# PCB-164D316B_sch.net
KiCad netlist of a schematic drawn in EAGLE
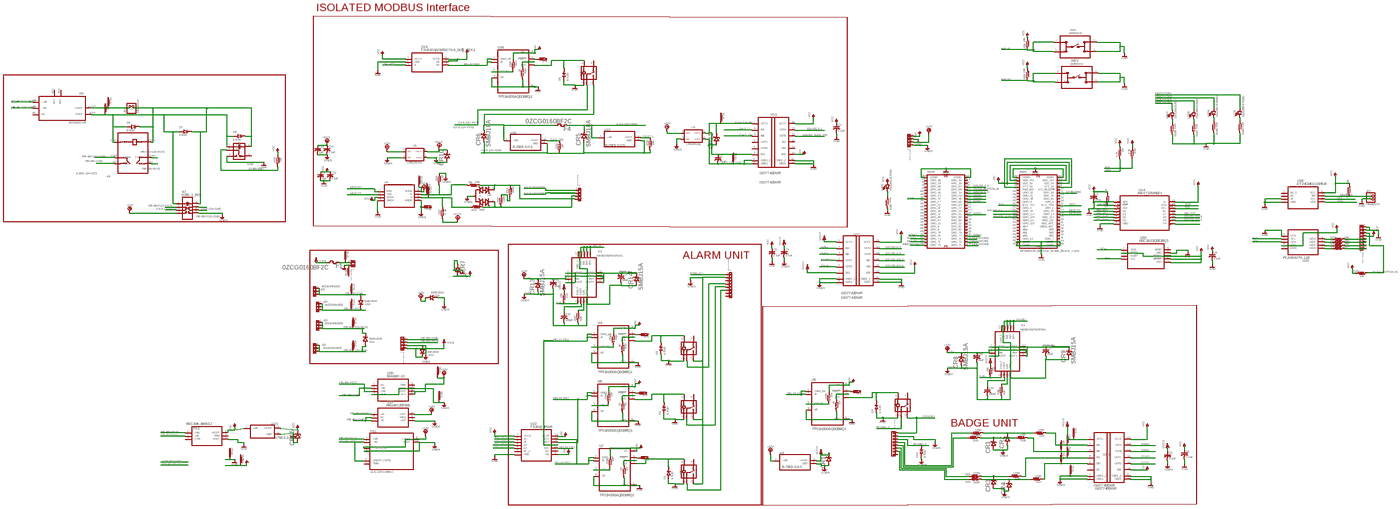
[diagram p0: schematic, sheet 1, overview]
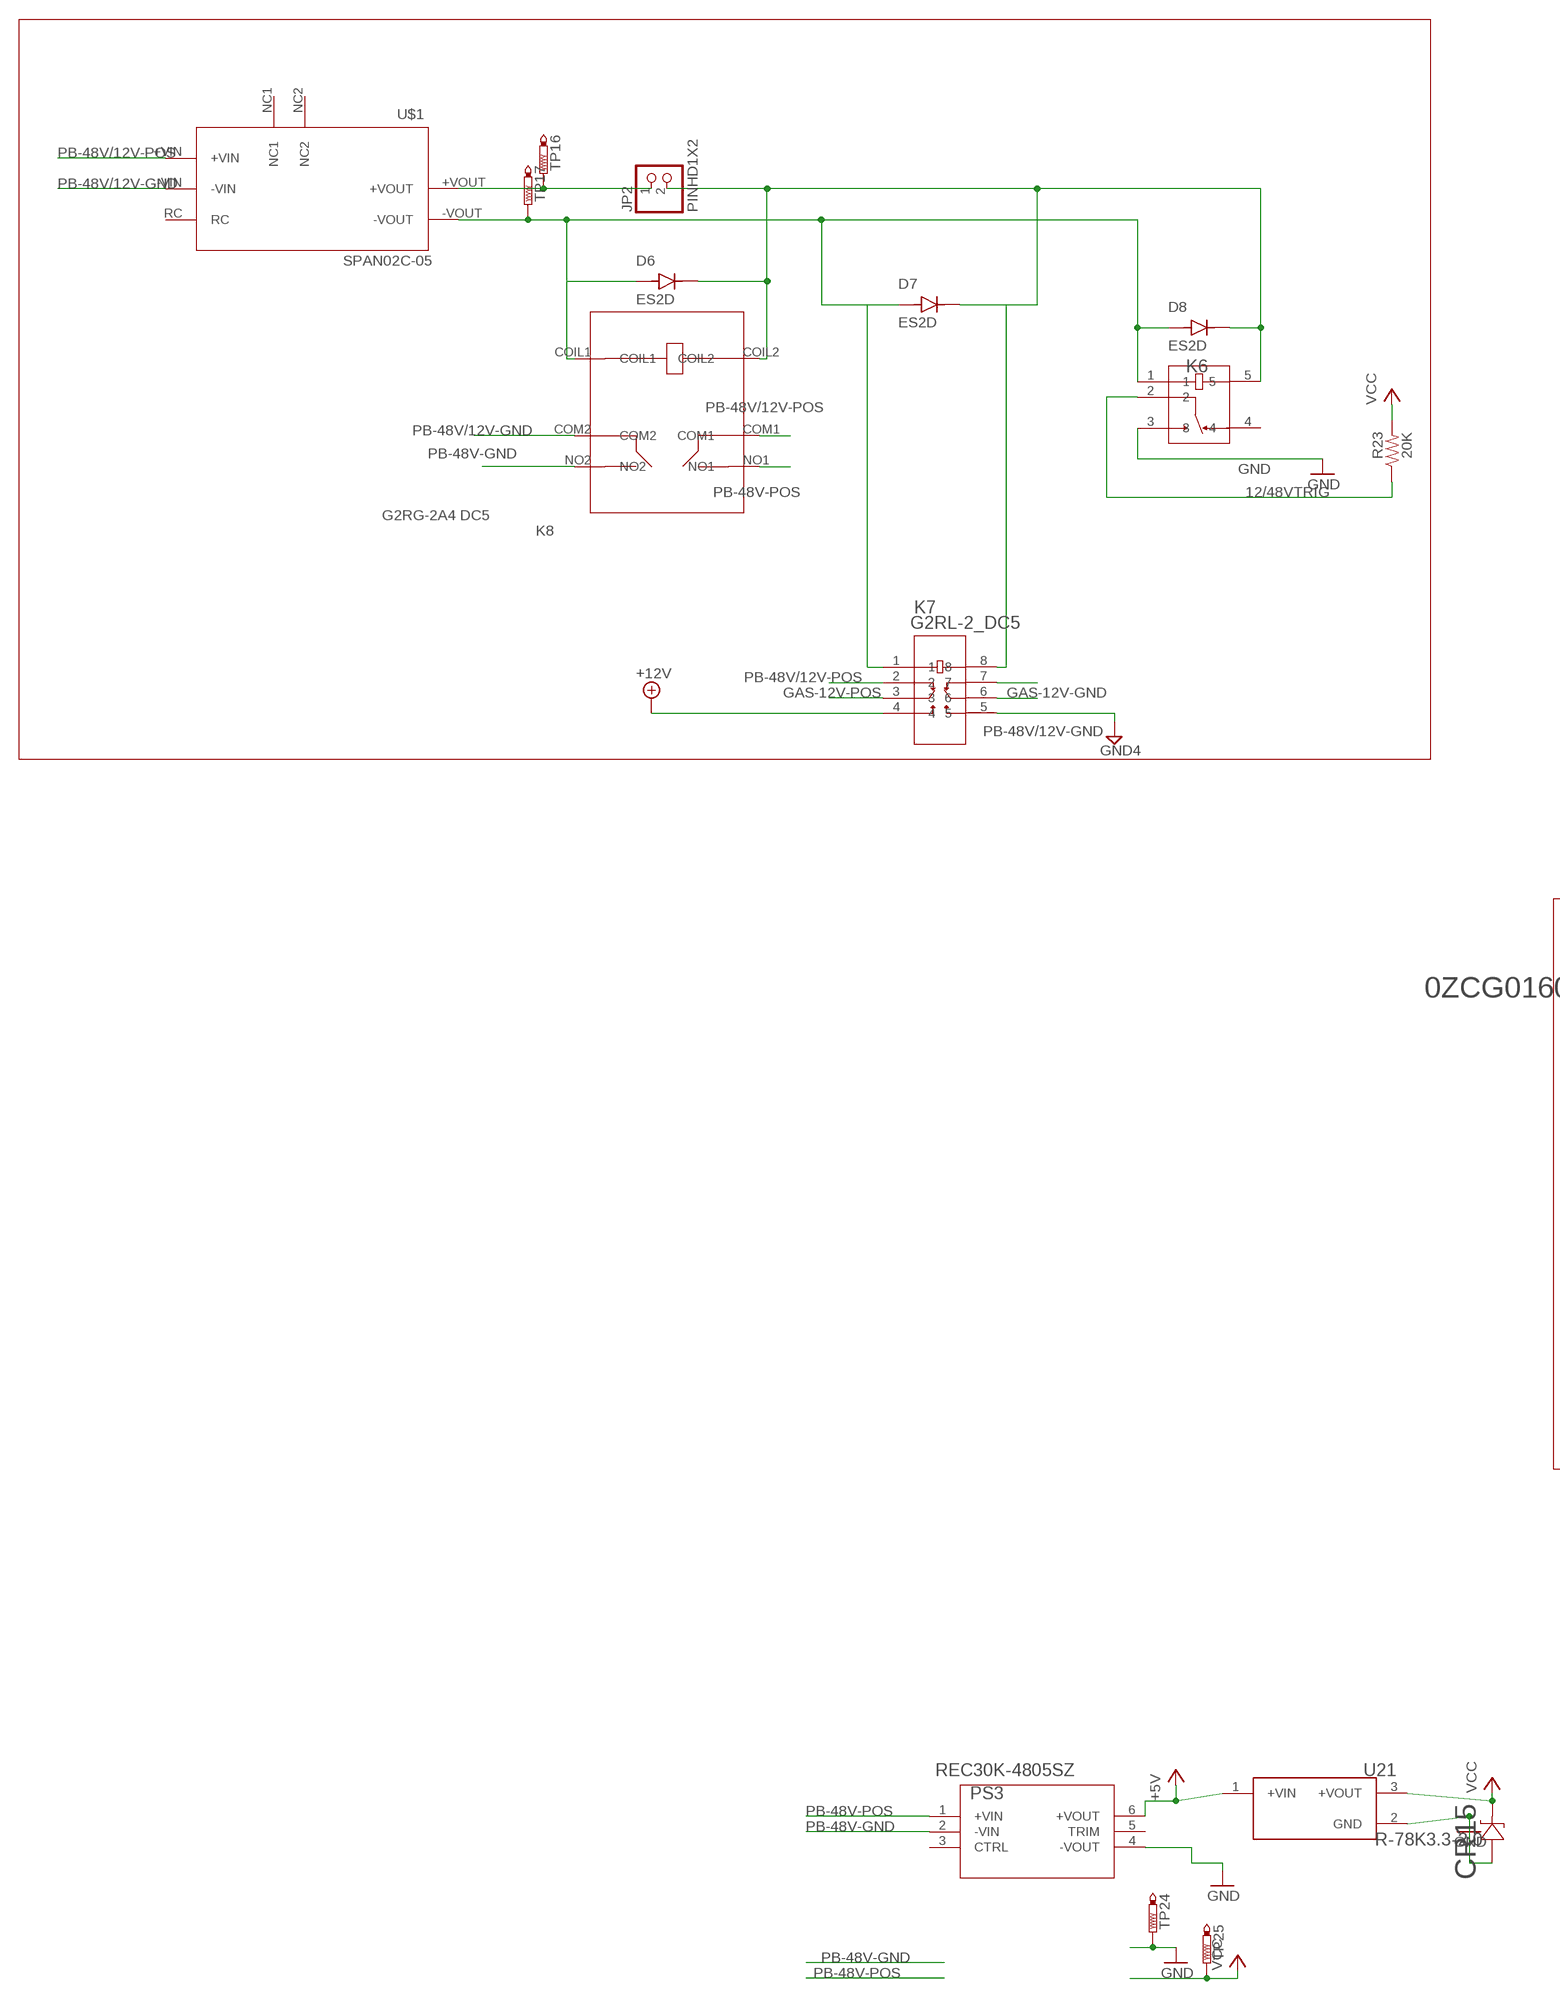
[diagram p1: schematic, sheet 1, part 1 of 4]
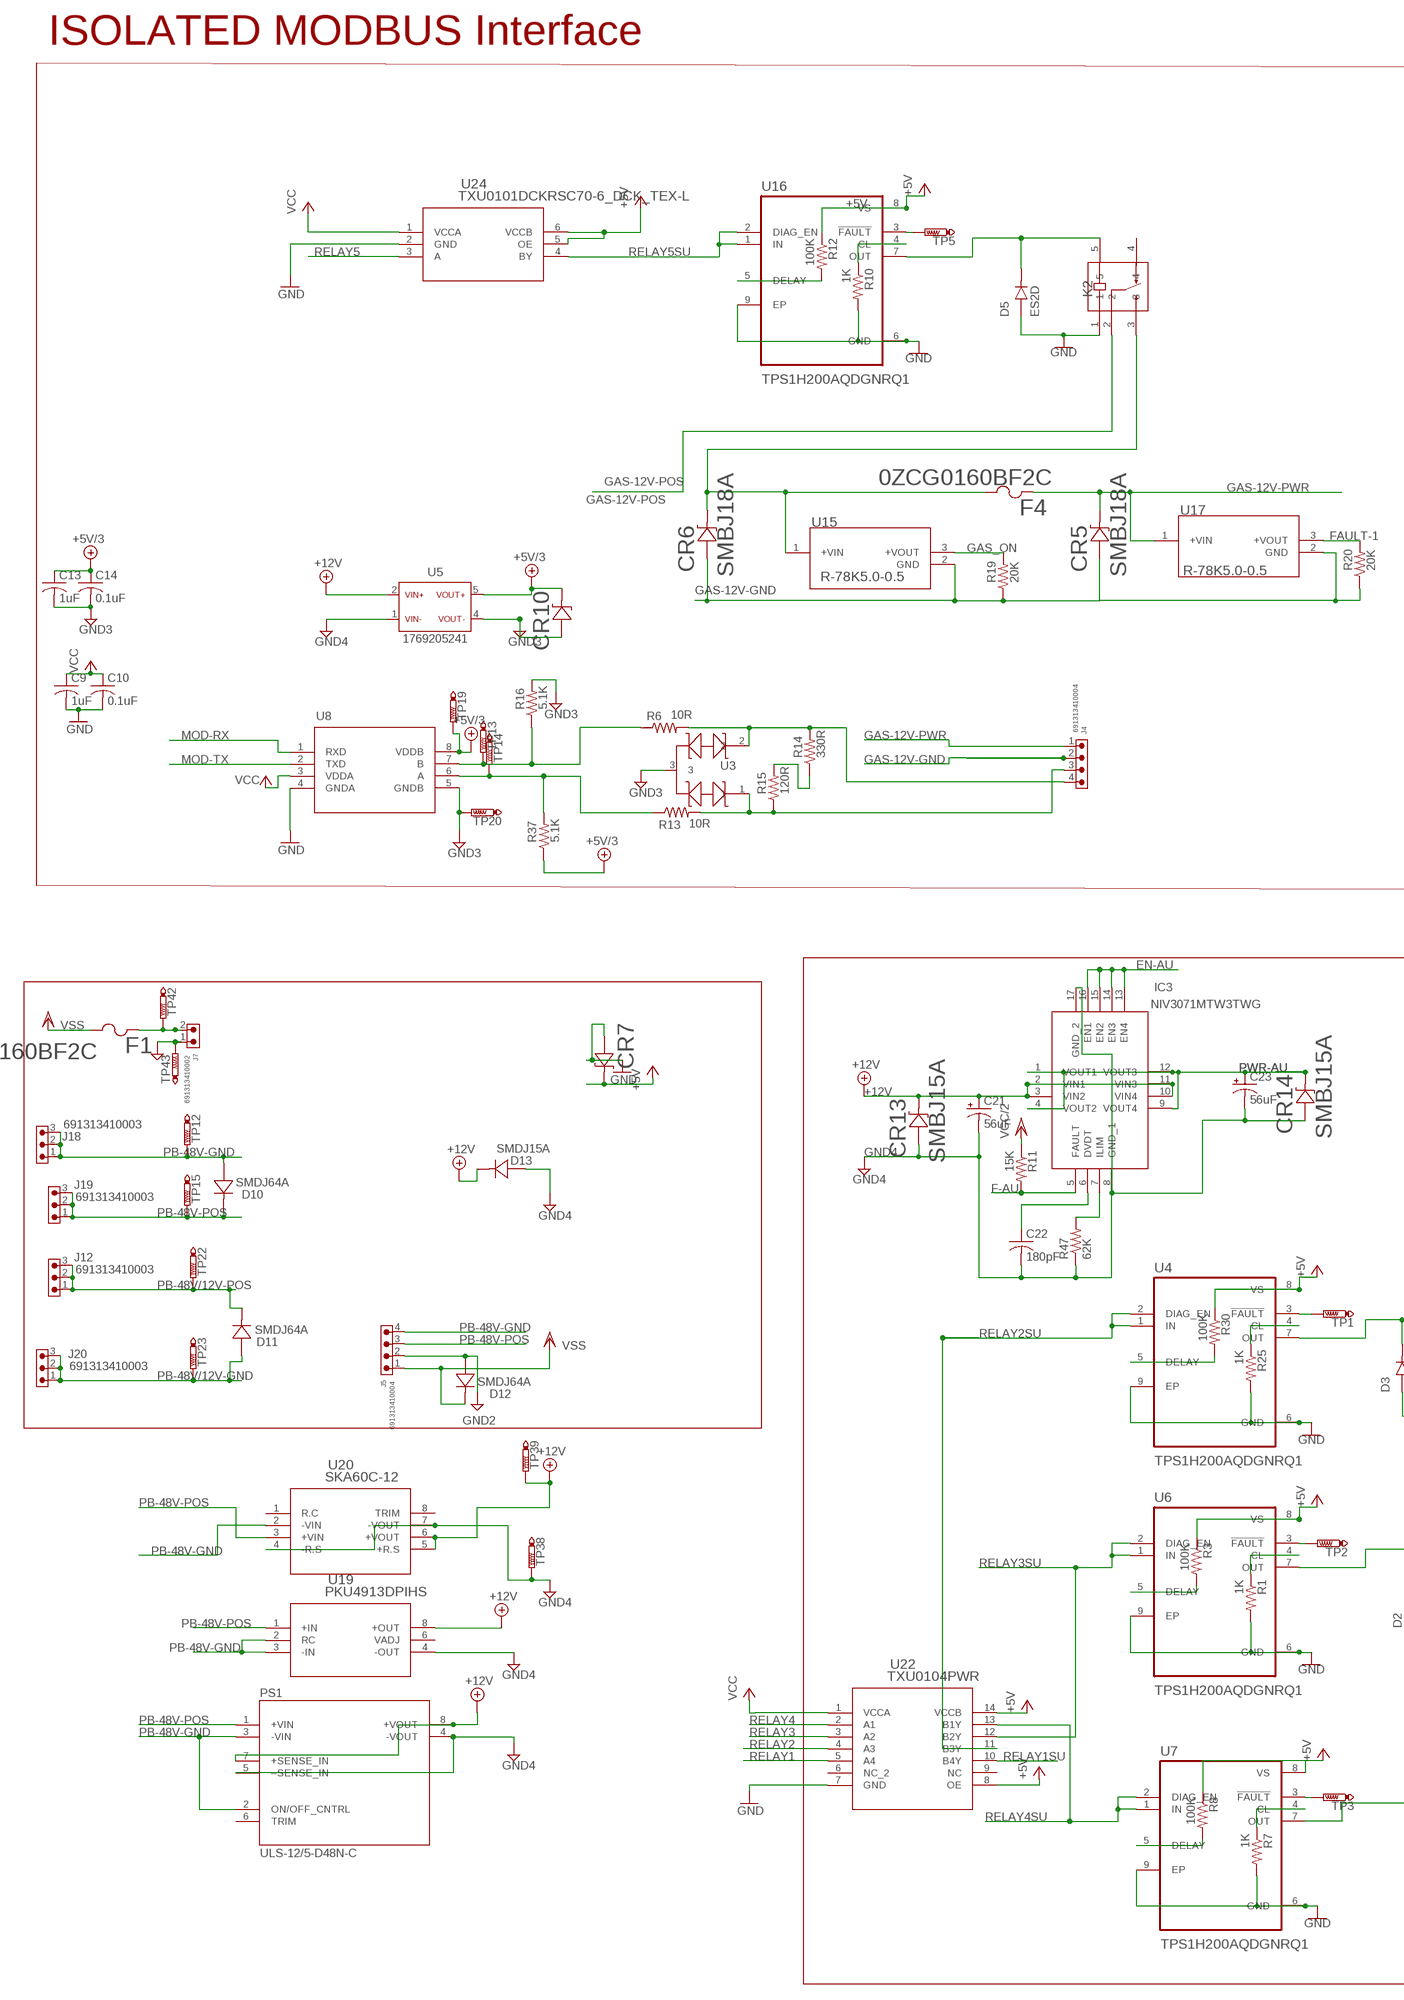
[diagram p2: schematic, sheet 1, part 2 of 4]
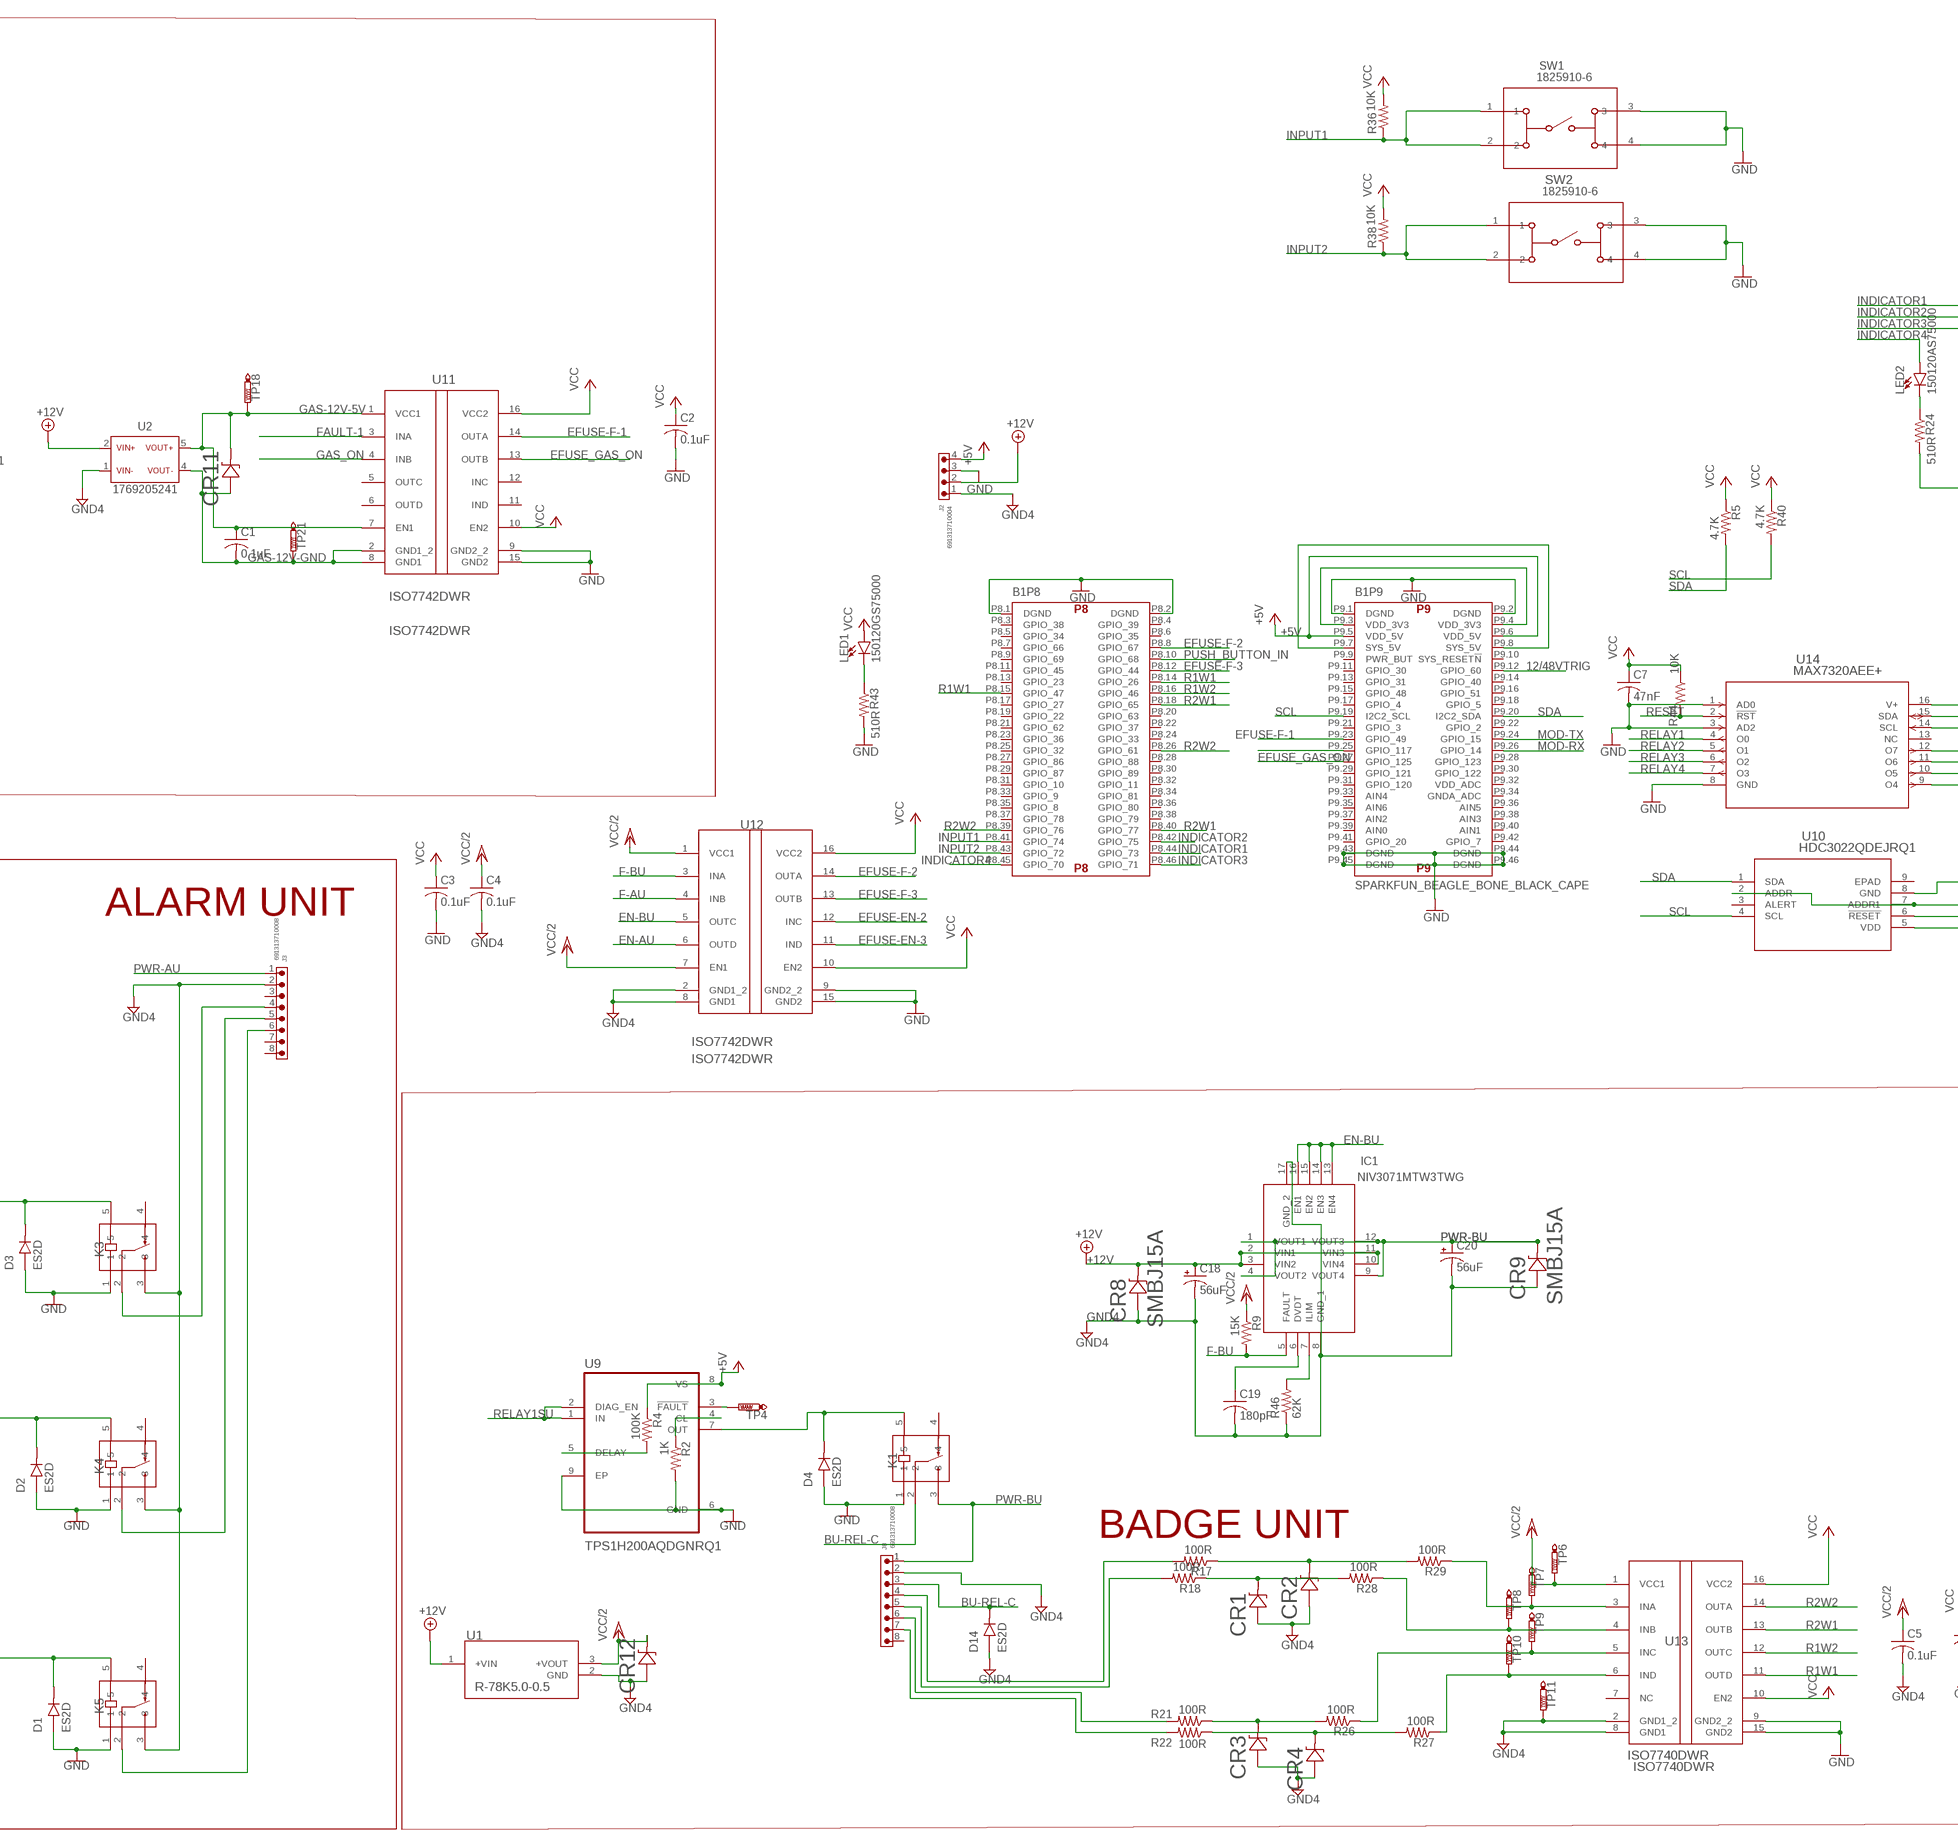
[diagram p3: schematic, sheet 1, part 3 of 4]
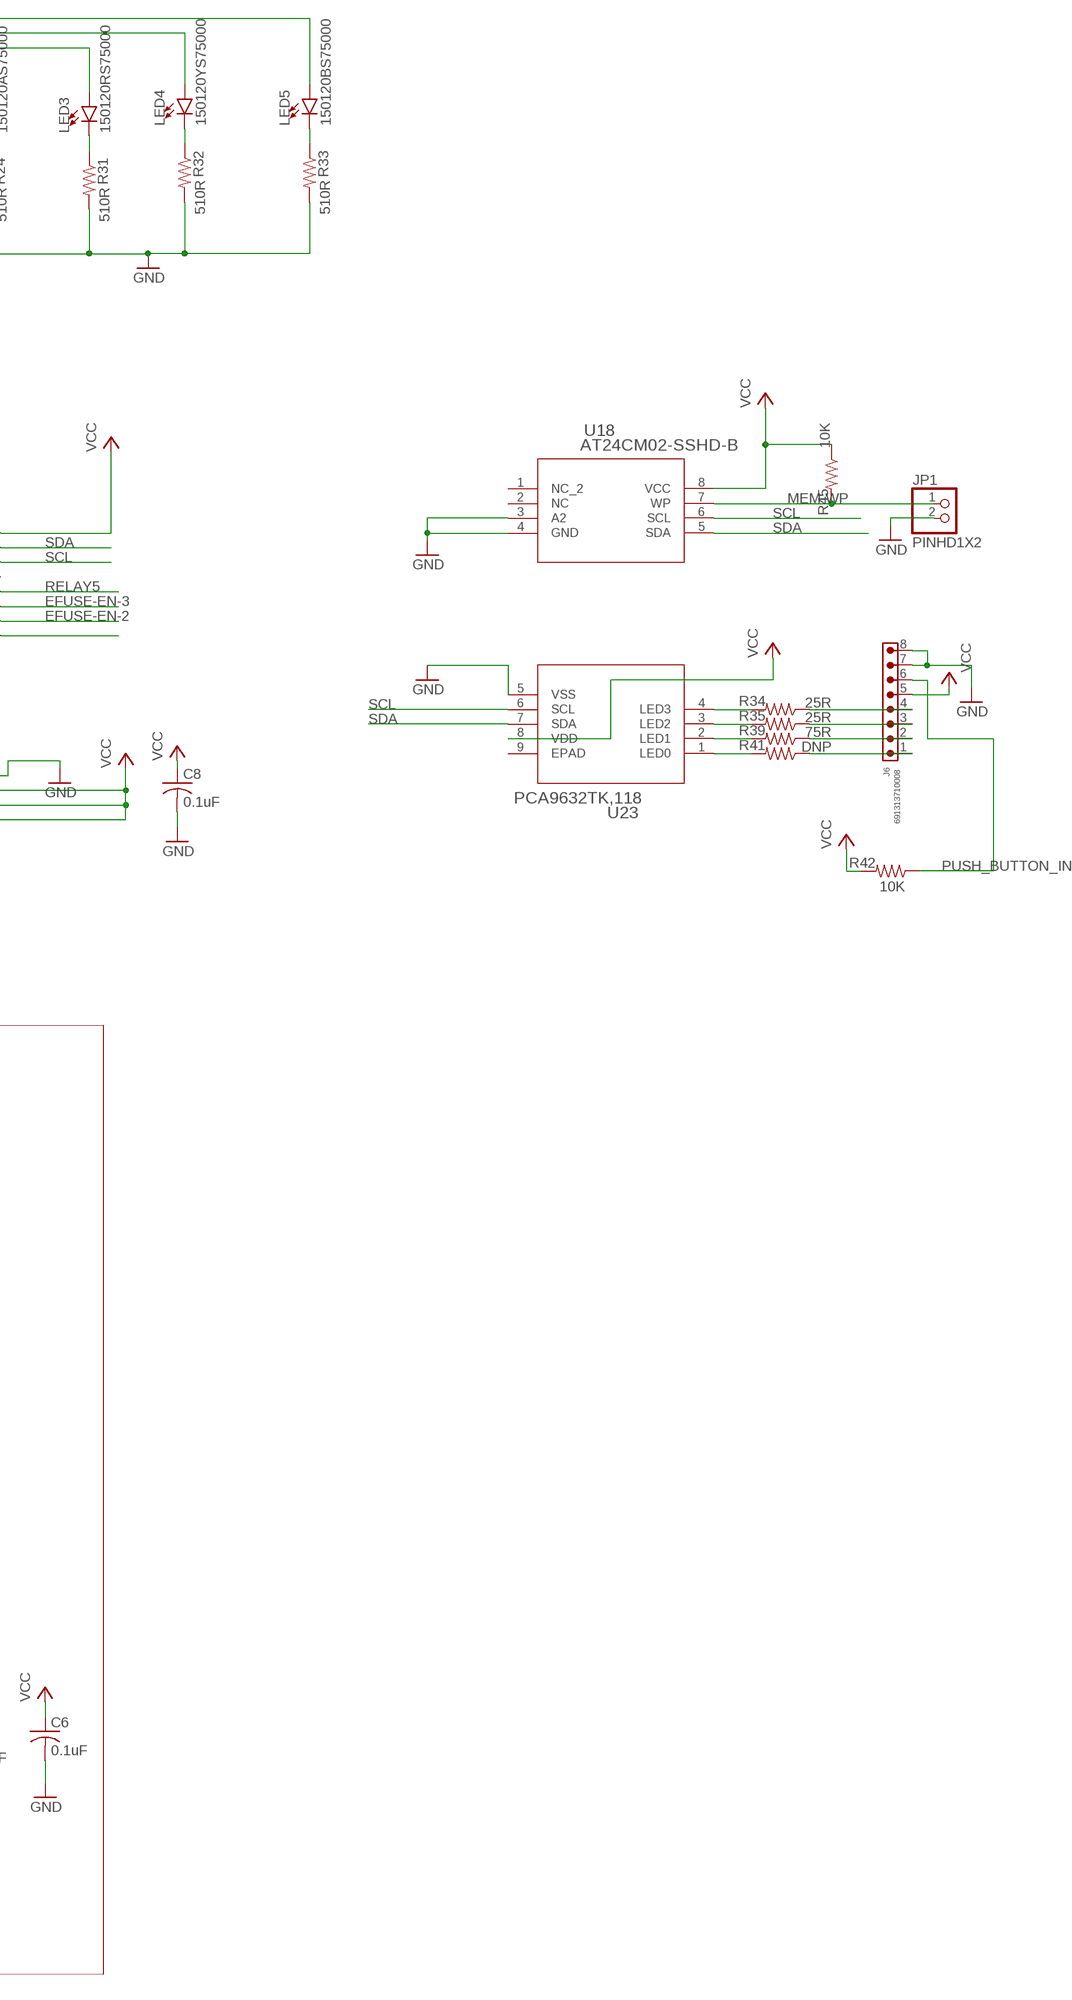
[diagram p4: schematic, sheet 1, part 4 of 4]

(export (version "E")
  (design (tool "Eeschema 10.0.6"))
  (components
    (comp (ref "B1")
      (value "SPARKFUN_BEAGLE_BONE_BLACK_CAPE")
      (footprint "eagle-import:BEAGLE_BONE_BLACK_CAPE")
      (libsource (lib "eagle-import") (part "SPARKFUN_BEAGLE_BONE_BLACK_CAPE"))
    )
    (comp (ref "C1")
      (value "0.1uF")
      (footprint "eagle-import:C1206")
      (libsource (lib "eagle-import") (part "C-USC1206"))
    )
    (comp (ref "C2")
      (value "0.1uF")
      (footprint "eagle-import:C1206")
      (libsource (lib "eagle-import") (part "C-USC1206"))
    )
    (comp (ref "C3")
      (value "0.1uF")
      (footprint "eagle-import:C1206")
      (libsource (lib "eagle-import") (part "C-USC1206"))
    )
    (comp (ref "C4")
      (value "0.1uF")
      (footprint "eagle-import:C1206")
      (libsource (lib "eagle-import") (part "C-USC1206"))
    )
    (comp (ref "C5")
      (value "0.1uF")
      (footprint "eagle-import:C1206")
      (libsource (lib "eagle-import") (part "C-USC1206"))
    )
    (comp (ref "C6")
      (value "0.1uF")
      (footprint "eagle-import:C1206")
      (libsource (lib "eagle-import") (part "C-USC1206"))
    )
    (comp (ref "C7")
      (value "47nF")
      (footprint "eagle-import:C1206")
      (libsource (lib "eagle-import") (part "C-USC1206"))
    )
    (comp (ref "C8")
      (value "0.1uF")
      (footprint "eagle-import:C1206")
      (libsource (lib "eagle-import") (part "C-USC1206"))
    )
    (comp (ref "C9")
      (value "1uF")
      (footprint "eagle-import:C1206")
      (libsource (lib "eagle-import") (part "C-USC1206"))
    )
    (comp (ref "C10")
      (value "0.1uF")
      (footprint "eagle-import:C1206")
      (libsource (lib "eagle-import") (part "C-USC1206"))
    )
    (comp (ref "C13")
      (value "1uF")
      (footprint "eagle-import:C1206")
      (libsource (lib "eagle-import") (part "C-USC1206"))
    )
    (comp (ref "C14")
      (value "0.1uF")
      (footprint "eagle-import:C1206")
      (libsource (lib "eagle-import") (part "C-USC1206"))
    )
    (comp (ref "C18")
      (value "56uF")
      (footprint "eagle-import:PANASONIC_C")
      (libsource (lib "eagle-import") (part "CPOL-USC"))
    )
    (comp (ref "C19")
      (value "180pF")
      (footprint "eagle-import:C1206")
      (libsource (lib "eagle-import") (part "C-USC1206"))
    )
    (comp (ref "C20")
      (value "56uF")
      (footprint "eagle-import:PANASONIC_C")
      (libsource (lib "eagle-import") (part "CPOL-USC"))
    )
    (comp (ref "C21")
      (value "56uF")
      (footprint "eagle-import:PANASONIC_C")
      (libsource (lib "eagle-import") (part "CPOL-USC"))
    )
    (comp (ref "C22")
      (value "180pF")
      (footprint "eagle-import:C1206")
      (libsource (lib "eagle-import") (part "C-USC1206"))
    )
    (comp (ref "C23")
      (value "56uF")
      (footprint "eagle-import:PANASONIC_C")
      (libsource (lib "eagle-import") (part "CPOL-USC"))
    )
    (comp (ref "CR1")
      (value "SMBJ6.0A")
      (footprint "eagle-import:DO-214AA(SMB_J-BEND)_LTF-M")
      (fields
        (field (name "MANUFACTURER_PART_NUMBER") "SMBJ5.0A")
        (field (name "COPYRIGHT") "Copyright (C) 2024 Ultra Librarian. All rights reserved.")
      )
      (libsource (lib "eagle-import") (part "SMBJ5.0ADO-214AA(SMB_J-BEND)_LTF-M"))
    )
    (comp (ref "CR2")
      (value "SMBJ6.0A")
      (footprint "eagle-import:DO-214AA(SMB_J-BEND)_LTF-M")
      (fields
        (field (name "MANUFACTURER_PART_NUMBER") "SMBJ5.0A")
        (field (name "COPYRIGHT") "Copyright (C) 2024 Ultra Librarian. All rights reserved.")
      )
      (libsource (lib "eagle-import") (part "SMBJ5.0ADO-214AA(SMB_J-BEND)_LTF-M"))
    )
    (comp (ref "CR3")
      (value "SMBJ6.0A")
      (footprint "eagle-import:DO-214AA(SMB_J-BEND)_LTF-M")
      (fields
        (field (name "MANUFACTURER_PART_NUMBER") "SMBJ5.0A")
        (field (name "COPYRIGHT") "Copyright (C) 2024 Ultra Librarian. All rights reserved.")
      )
      (libsource (lib "eagle-import") (part "SMBJ5.0ADO-214AA(SMB_J-BEND)_LTF-M"))
    )
    (comp (ref "CR4")
      (value "SMBJ6.0A")
      (footprint "eagle-import:DO-214AA(SMB_J-BEND)_LTF-M")
      (fields
        (field (name "MANUFACTURER_PART_NUMBER") "SMBJ5.0A")
        (field (name "COPYRIGHT") "Copyright (C) 2024 Ultra Librarian. All rights reserved.")
      )
      (libsource (lib "eagle-import") (part "SMBJ5.0ADO-214AA(SMB_J-BEND)_LTF-M"))
    )
    (comp (ref "CR5")
      (value "SMBJ18A")
      (footprint "eagle-import:DO-214AA(SMB_J-BEND)_LTF-M")
      (fields
        (field (name "MANUFACTURER_PART_NUMBER") "SMBJ5.0A")
        (field (name "COPYRIGHT") "Copyright (C) 2024 Ultra Librarian. All rights reserved.")
      )
      (libsource (lib "eagle-import") (part "SMBJ5.0ADO-214AA(SMB_J-BEND)_LTF-M"))
    )
    (comp (ref "CR6")
      (value "SMBJ18A")
      (footprint "eagle-import:DO-214AA(SMB_J-BEND)_LTF-M")
      (fields
        (field (name "MANUFACTURER_PART_NUMBER") "SMBJ5.0A")
        (field (name "COPYRIGHT") "Copyright (C) 2024 Ultra Librarian. All rights reserved.")
      )
      (libsource (lib "eagle-import") (part "SMBJ5.0ADO-214AA(SMB_J-BEND)_LTF-M"))
    )
    (comp (ref "CR7")
      (value "SMBJ6.0A")
      (footprint "eagle-import:DO-214AA(SMB_J-BEND)_LTF-M")
      (fields
        (field (name "MANUFACTURER_PART_NUMBER") "SMBJ5.0A")
        (field (name "COPYRIGHT") "Copyright (C) 2024 Ultra Librarian. All rights reserved.")
      )
      (libsource (lib "eagle-import") (part "SMBJ5.0ADO-214AA(SMB_J-BEND)_LTF-M"))
    )
    (comp (ref "CR8")
      (value "SMBJ15A")
      (footprint "eagle-import:DO-214AA(SMB_J-BEND)_LTF-M")
      (fields
        (field (name "MANUFACTURER_PART_NUMBER") "SMBJ5.0A")
        (field (name "COPYRIGHT") "Copyright (C) 2024 Ultra Librarian. All rights reserved.")
      )
      (libsource (lib "eagle-import") (part "SMBJ5.0ADO-214AA(SMB_J-BEND)_LTF-M"))
    )
    (comp (ref "CR9")
      (value "SMBJ15A")
      (footprint "eagle-import:DO-214AA(SMB_J-BEND)_LTF-M")
      (fields
        (field (name "MANUFACTURER_PART_NUMBER") "SMBJ5.0A")
        (field (name "COPYRIGHT") "Copyright (C) 2024 Ultra Librarian. All rights reserved.")
      )
      (libsource (lib "eagle-import") (part "SMBJ5.0ADO-214AA(SMB_J-BEND)_LTF-M"))
    )
    (comp (ref "CR10")
      (value "SMBJ6.0A")
      (footprint "eagle-import:DO-214AA(SMB_J-BEND)_LTF-M")
      (fields
        (field (name "MANUFACTURER_PART_NUMBER") "SMBJ5.0A")
        (field (name "COPYRIGHT") "Copyright (C) 2024 Ultra Librarian. All rights reserved.")
      )
      (libsource (lib "eagle-import") (part "SMBJ5.0ADO-214AA(SMB_J-BEND)_LTF-M"))
    )
    (comp (ref "CR11")
      (value "SMBJ6.0A")
      (footprint "eagle-import:DO-214AA(SMB_J-BEND)_LTF-M")
      (fields
        (field (name "MANUFACTURER_PART_NUMBER") "SMBJ5.0A")
        (field (name "COPYRIGHT") "Copyright (C) 2024 Ultra Librarian. All rights reserved.")
      )
      (libsource (lib "eagle-import") (part "SMBJ5.0ADO-214AA(SMB_J-BEND)_LTF-M"))
    )
    (comp (ref "CR12")
      (value "SMBJ6.0A")
      (footprint "eagle-import:DO-214AA(SMB_J-BEND)_LTF-M")
      (fields
        (field (name "MANUFACTURER_PART_NUMBER") "SMBJ5.0A")
        (field (name "COPYRIGHT") "Copyright (C) 2024 Ultra Librarian. All rights reserved.")
      )
      (libsource (lib "eagle-import") (part "SMBJ5.0ADO-214AA(SMB_J-BEND)_LTF-M"))
    )
    (comp (ref "CR13")
      (value "SMBJ15A")
      (footprint "eagle-import:DO-214AA(SMB_J-BEND)_LTF-M")
      (fields
        (field (name "MANUFACTURER_PART_NUMBER") "SMBJ5.0A")
        (field (name "COPYRIGHT") "Copyright (C) 2024 Ultra Librarian. All rights reserved.")
      )
      (libsource (lib "eagle-import") (part "SMBJ5.0ADO-214AA(SMB_J-BEND)_LTF-M"))
    )
    (comp (ref "CR14")
      (value "SMBJ15A")
      (footprint "eagle-import:DO-214AA(SMB_J-BEND)_LTF-M")
      (fields
        (field (name "MANUFACTURER_PART_NUMBER") "SMBJ5.0A")
        (field (name "COPYRIGHT") "Copyright (C) 2024 Ultra Librarian. All rights reserved.")
      )
      (libsource (lib "eagle-import") (part "SMBJ5.0ADO-214AA(SMB_J-BEND)_LTF-M"))
    )
    (comp (ref "CR15")
      (value "SMBJ6.0A")
      (footprint "eagle-import:DO-214AA(SMB_J-BEND)_LTF-M")
      (fields
        (field (name "MANUFACTURER_PART_NUMBER") "SMBJ5.0A")
        (field (name "COPYRIGHT") "Copyright (C) 2024 Ultra Librarian. All rights reserved.")
      )
      (libsource (lib "eagle-import") (part "SMBJ5.0ADO-214AA(SMB_J-BEND)_LTF-M"))
    )
    (comp (ref "D1")
      (value "ES2D")
      (footprint "eagle-import:DIOM4336X265N")
      (fields
        (field (name "DIGIKEY_PART_NUMBER") "1801-ES2DTR-ND")
        (field (name "MF") "Taiwan Semiconductor")
      )
      (libsource (lib "eagle-import") (part "ES2D"))
    )
    (comp (ref "D2")
      (value "ES2D")
      (footprint "eagle-import:DIOM4336X265N")
      (fields
        (field (name "DIGIKEY_PART_NUMBER") "1801-ES2DTR-ND")
        (field (name "MF") "Taiwan Semiconductor")
      )
      (libsource (lib "eagle-import") (part "ES2D"))
    )
    (comp (ref "D3")
      (value "ES2D")
      (footprint "eagle-import:DIOM4336X265N")
      (fields
        (field (name "DIGIKEY_PART_NUMBER") "1801-ES2DTR-ND")
        (field (name "MF") "Taiwan Semiconductor")
      )
      (libsource (lib "eagle-import") (part "ES2D"))
    )
    (comp (ref "D4")
      (value "ES2D")
      (footprint "eagle-import:DIOM4336X265N")
      (fields
        (field (name "DIGIKEY_PART_NUMBER") "1801-ES2DTR-ND")
        (field (name "MF") "Taiwan Semiconductor")
      )
      (libsource (lib "eagle-import") (part "ES2D"))
    )
    (comp (ref "D5")
      (value "ES2D")
      (footprint "eagle-import:DIOM4336X265N")
      (fields
        (field (name "DIGIKEY_PART_NUMBER") "1801-ES2DTR-ND")
        (field (name "MF") "Taiwan Semiconductor")
      )
      (libsource (lib "eagle-import") (part "ES2D"))
    )
    (comp (ref "D6")
      (value "ES2D")
      (footprint "eagle-import:DIOM4336X265N")
      (fields
        (field (name "DIGIKEY_PART_NUMBER") "1801-ES2DTR-ND")
        (field (name "MF") "Taiwan Semiconductor")
      )
      (libsource (lib "eagle-import") (part "ES2D"))
    )
    (comp (ref "D7")
      (value "ES2D")
      (footprint "eagle-import:DIOM4336X265N")
      (fields
        (field (name "DIGIKEY_PART_NUMBER") "1801-ES2DTR-ND")
        (field (name "MF") "Taiwan Semiconductor")
      )
      (libsource (lib "eagle-import") (part "ES2D"))
    )
    (comp (ref "D8")
      (value "ES2D")
      (footprint "eagle-import:DIOM4336X265N")
      (fields
        (field (name "DIGIKEY_PART_NUMBER") "1801-ES2DTR-ND")
        (field (name "MF") "Taiwan Semiconductor")
      )
      (libsource (lib "eagle-import") (part "ES2D"))
    )
    (comp (ref "D10")
      (value "SMDJ64A")
      (footprint "eagle-import:SMDJSERIES_LTF-M")
      (fields (field (name "COPYRIGHT") "Copyright (C) 2025 Ultra Librarian. All rights reserved."))
      (libsource (lib "eagle-import") (part "SMDJ64ASMDJSERIES_LTF-M"))
    )
    (comp (ref "D11")
      (value "SMDJ64A")
      (footprint "eagle-import:SMDJSERIES_LTF-M")
      (fields (field (name "COPYRIGHT") "Copyright (C) 2025 Ultra Librarian. All rights reserved."))
      (libsource (lib "eagle-import") (part "SMDJ64ASMDJSERIES_LTF-M"))
    )
    (comp (ref "D12")
      (value "SMDJ64A")
      (footprint "eagle-import:SMDJSERIES_LTF-M")
      (fields (field (name "COPYRIGHT") "Copyright (C) 2025 Ultra Librarian. All rights reserved."))
      (libsource (lib "eagle-import") (part "SMDJ64ASMDJSERIES_LTF-M"))
    )
    (comp (ref "D13")
      (value "SMDJ15A")
      (footprint "eagle-import:SMDJSERIES_LTF-M")
      (fields
        (field (name "MANUFACTURER_PART_NUMBER") "SMDJ64A")
        (field (name "COPYRIGHT") "Copyright (C) 2025 Ultra Librarian. All rights reserved.")
      )
      (libsource (lib "eagle-import") (part "SMDJ64ASMDJSERIES_LTF-M"))
    )
    (comp (ref "D14")
      (value "ES2D")
      (footprint "eagle-import:DIOM4336X265N")
      (fields
        (field (name "DIGIKEY_PART_NUMBER") "1801-ES2DTR-ND")
        (field (name "MF") "Taiwan Semiconductor")
      )
      (libsource (lib "eagle-import") (part "ES2D"))
    )
    (comp (ref "F1")
      (value "0ZCG0160BF2C")
      (footprint "eagle-import:0ZCG_BEL")
      (fields (field (name "COPYRIGHT") "Copyright (C) 2024 Ultra Librarian. All rights reserved."))
      (libsource (lib "eagle-import") (part "0ZCG0160BF2C0ZCG_BEL"))
    )
    (comp (ref "F4")
      (value "0ZCG0160BF2C")
      (footprint "eagle-import:0ZCG_BEL")
      (fields (field (name "COPYRIGHT") "Copyright (C) 2024 Ultra Librarian. All rights reserved."))
      (libsource (lib "eagle-import") (part "0ZCG0160BF2C0ZCG_BEL"))
    )
    (comp (ref "IC1")
      (value "NIV3071MTW3TWG")
      (footprint "eagle-import:QFN105P500X600X80-17N")
      (fields (field (name "MOUSER_PART_NUMBER") "863-NIV3071MTW3TWG"))
      (libsource (lib "eagle-import") (part "NIV3071MTW3TWG"))
    )
    (comp (ref "IC3")
      (value "NIV3071MTW3TWG")
      (footprint "eagle-import:QFN105P500X600X80-17N")
      (fields (field (name "MOUSER_PART_NUMBER") "863-NIV3071MTW3TWG"))
      (libsource (lib "eagle-import") (part "NIV3071MTW3TWG"))
    )
    (comp (ref "J2")
      (value "691313710004")
      (footprint "eagle-import:691313710004")
      (libsource (lib "eagle-import") (part "691313710004"))
    )
    (comp (ref "J3")
      (value "691313710008")
      (footprint "eagle-import:691313710008")
      (libsource (lib "eagle-import") (part "691313710008"))
    )
    (comp (ref "J4")
      (value "691313410004")
      (footprint "eagle-import:691313410004")
      (libsource (lib "eagle-import") (part "691313410004"))
    )
    (comp (ref "J5")
      (value "691313410004")
      (footprint "eagle-import:691313410004")
      (libsource (lib "eagle-import") (part "691313410004"))
    )
    (comp (ref "J6")
      (value "691313710008")
      (footprint "eagle-import:691313710008")
      (libsource (lib "eagle-import") (part "691313710008"))
    )
    (comp (ref "J7")
      (value "691313410002")
      (footprint "eagle-import:691313410002")
      (libsource (lib "eagle-import") (part "691313410002"))
    )
    (comp (ref "J8")
      (value "691313710008")
      (footprint "eagle-import:691313710008")
      (libsource (lib "eagle-import") (part "691313710008"))
    )
    (comp (ref "J12")
      (value "691313410003")
      (footprint "eagle-import:691313410003")
      (libsource (lib "eagle-import") (part "691313410003"))
    )
    (comp (ref "J18")
      (value "691313410003")
      (footprint "eagle-import:691313410003")
      (libsource (lib "eagle-import") (part "691313410003"))
    )
    (comp (ref "J19")
      (value "691313410003")
      (footprint "eagle-import:691313410003")
      (libsource (lib "eagle-import") (part "691313410003"))
    )
    (comp (ref "J20")
      (value "691313410003")
      (footprint "eagle-import:691313410003")
      (libsource (lib "eagle-import") (part "691313410003"))
    )
    (comp (ref "JP1")
      (value "PINHD1X2")
      (footprint "eagle-import:1X02")
      (libsource (lib "eagle-import") (part "PINHD-1X2"))
    )
    (comp (ref "JP2")
      (value "PINHD1X2")
      (footprint "eagle-import:1X02")
      (libsource (lib "eagle-import") (part "PINHD-1X2"))
    )
    (comp (ref "K1")
      (value "G5Q-14_DC5")
      (footprint "eagle-import:RELAY_G5Q-1_DC5_OMR")
      (fields
        (field (name "MANUFACTURER_PART_NUMBER") "G5Q-14 DC5")
        (field (name "COPYRIGHT") "Copyright (C) 2024 Ultra Librarian. All rights reserved.")
      )
      (libsource (lib "eagle-import") (part "G5Q-14_DC5RELAY_G5Q-1_DC5_OMR"))
    )
    (comp (ref "K2")
      (value "G5Q-14_DC5")
      (footprint "eagle-import:RELAY_G5Q-1_DC5_OMR")
      (fields
        (field (name "MANUFACTURER_PART_NUMBER") "G5Q-14 DC5")
        (field (name "COPYRIGHT") "Copyright (C) 2024 Ultra Librarian. All rights reserved.")
      )
      (libsource (lib "eagle-import") (part "G5Q-14_DC5RELAY_G5Q-1_DC5_OMR"))
    )
    (comp (ref "K3")
      (value "G5Q-14_DC5")
      (footprint "eagle-import:RELAY_G5Q-1_DC5_OMR")
      (fields
        (field (name "MANUFACTURER_PART_NUMBER") "G5Q-14 DC5")
        (field (name "COPYRIGHT") "Copyright (C) 2024 Ultra Librarian. All rights reserved.")
      )
      (libsource (lib "eagle-import") (part "G5Q-14_DC5RELAY_G5Q-1_DC5_OMR"))
    )
    (comp (ref "K4")
      (value "G5Q-14_DC5")
      (footprint "eagle-import:RELAY_G5Q-1_DC5_OMR")
      (fields
        (field (name "MANUFACTURER_PART_NUMBER") "G5Q-14 DC5")
        (field (name "COPYRIGHT") "Copyright (C) 2024 Ultra Librarian. All rights reserved.")
      )
      (libsource (lib "eagle-import") (part "G5Q-14_DC5RELAY_G5Q-1_DC5_OMR"))
    )
    (comp (ref "K5")
      (value "G5Q-14_DC5")
      (footprint "eagle-import:RELAY_G5Q-1_DC5_OMR")
      (fields
        (field (name "MANUFACTURER_PART_NUMBER") "G5Q-14 DC5")
        (field (name "COPYRIGHT") "Copyright (C) 2024 Ultra Librarian. All rights reserved.")
      )
      (libsource (lib "eagle-import") (part "G5Q-14_DC5RELAY_G5Q-1_DC5_OMR"))
    )
    (comp (ref "K6")
      (value "G5Q-14_DC5")
      (footprint "eagle-import:RELAY_G5Q-1_DC5_OMR")
      (fields
        (field (name "MANUFACTURER_PART_NUMBER") "G5Q-14 DC5")
        (field (name "COPYRIGHT") "Copyright (C) 2024 Ultra Librarian. All rights reserved.")
      )
      (libsource (lib "eagle-import") (part "G5Q-14_DC5RELAY_G5Q-1_DC5_OMR"))
    )
    (comp (ref "K7")
      (value "G2RL-2_DC5")
      (footprint "eagle-import:RELAY_G2RL-2_OMR")
      (fields
        (field (name "MANUFACTURER_PART_NUMBER") "G2RL-2 DC5")
        (field (name "COPYRIGHT") "Copyright (C) 2025 Ultra Librarian. All rights reserved.")
      )
      (libsource (lib "eagle-import") (part "G2RL-2_DC5RELAY_G2RL-2_OMR"))
    )
    (comp (ref "K8")
      (value "G2RG-2A4 DC5")
      (footprint "eagle-import:G2RG-2A4")
      (libsource (lib "eagle-import") (part "OMRON_G2RG-2A-XDC12"))
    )
    (comp (ref "LED1")
      (value "150120GS75000")
      (footprint "eagle-import:LED-1206")
      (libsource (lib "eagle-import") (part "LED1206"))
    )
    (comp (ref "LED2")
      (value "150120AS75000")
      (footprint "eagle-import:LED-1206")
      (libsource (lib "eagle-import") (part "LED1206"))
    )
    (comp (ref "LED3")
      (value "150120RS75000")
      (footprint "eagle-import:LED-1206")
      (libsource (lib "eagle-import") (part "LED1206"))
    )
    (comp (ref "LED4")
      (value "150120YS75000")
      (footprint "eagle-import:LED-1206")
      (libsource (lib "eagle-import") (part "LED1206"))
    )
    (comp (ref "LED5")
      (value "150120BS75000")
      (footprint "eagle-import:LED-1206")
      (libsource (lib "eagle-import") (part "LED1206"))
    )
    (comp (ref "PS1")
      (value "ULS-12/5-D48N-C")
      (footprint "eagle-import:CONV_ULS-12_5-D48N-C")
      (fields (field (name "MANUFACTURER") "MURATA POWER SOLUTIONS"))
      (libsource (lib "eagle-import") (part "ULS-12/5-D48N-C"))
    )
    (comp (ref "PS3")
      (value "REC30K-4805SZ")
      (footprint "eagle-import:REC20K_RCP")
      (fields
        (field (name "MANUFACTURER_PART_NUMBER") "REC20K-2405SZ")
        (field (name "COPYRIGHT") "Copyright (C) 2025 Ultra Librarian. All rights reserved.")
      )
      (libsource (lib "eagle-import") (part "REC20K-2405SZREC20K_RCP"))
    )
    (comp (ref "R1")
      (value "1K")
      (footprint "eagle-import:R1206")
      (libsource (lib "eagle-import") (part "R-US_R1206"))
    )
    (comp (ref "R2")
      (value "1K")
      (footprint "eagle-import:R1206")
      (libsource (lib "eagle-import") (part "R-US_R1206"))
    )
    (comp (ref "R3")
      (value "100K")
      (footprint "eagle-import:R1206")
      (libsource (lib "eagle-import") (part "R-US_R1206"))
    )
    (comp (ref "R4")
      (value "100K")
      (footprint "eagle-import:R1206")
      (libsource (lib "eagle-import") (part "R-US_R1206"))
    )
    (comp (ref "R5")
      (value "4.7K")
      (footprint "eagle-import:R1206")
      (libsource (lib "eagle-import") (part "R-US_R1206"))
    )
    (comp (ref "R6")
      (value "10R")
      (footprint "eagle-import:R1206")
      (libsource (lib "eagle-import") (part "R-US_R1206"))
    )
    (comp (ref "R7")
      (value "1K")
      (footprint "eagle-import:R1206")
      (libsource (lib "eagle-import") (part "R-US_R1206"))
    )
    (comp (ref "R8")
      (value "100K")
      (footprint "eagle-import:R1206")
      (libsource (lib "eagle-import") (part "R-US_R1206"))
    )
    (comp (ref "R9")
      (value "15K")
      (footprint "eagle-import:R1206")
      (libsource (lib "eagle-import") (part "R-US_R1206"))
    )
    (comp (ref "R10")
      (value "1K")
      (footprint "eagle-import:R1206")
      (libsource (lib "eagle-import") (part "R-US_R1206"))
    )
    (comp (ref "R11")
      (value "15K")
      (footprint "eagle-import:R1206")
      (libsource (lib "eagle-import") (part "R-US_R1206"))
    )
    (comp (ref "R12")
      (value "100K")
      (footprint "eagle-import:R1206")
      (libsource (lib "eagle-import") (part "R-US_R1206"))
    )
    (comp (ref "R13")
      (value "10R")
      (footprint "eagle-import:R1206")
      (libsource (lib "eagle-import") (part "R-US_R1206"))
    )
    (comp (ref "R14")
      (value "330R")
      (footprint "eagle-import:R1206")
      (libsource (lib "eagle-import") (part "R-US_R1206"))
    )
    (comp (ref "R15")
      (value "120R")
      (footprint "eagle-import:R1206")
      (libsource (lib "eagle-import") (part "R-US_R1206"))
    )
    (comp (ref "R16")
      (value "5.1K")
      (footprint "eagle-import:R1206")
      (libsource (lib "eagle-import") (part "R-US_R1206"))
    )
    (comp (ref "R17")
      (value "100R")
      (footprint "eagle-import:R1206")
      (libsource (lib "eagle-import") (part "R-US_R1206"))
    )
    (comp (ref "R18")
      (value "100R")
      (footprint "eagle-import:R1206")
      (libsource (lib "eagle-import") (part "R-US_R1206"))
    )
    (comp (ref "R19")
      (value "20K")
      (footprint "eagle-import:R1206")
      (libsource (lib "eagle-import") (part "R-US_R1206"))
    )
    (comp (ref "R20")
      (value "20K")
      (footprint "eagle-import:R1206")
      (libsource (lib "eagle-import") (part "R-US_R1206"))
    )
    (comp (ref "R21")
      (value "100R")
      (footprint "eagle-import:R1206")
      (libsource (lib "eagle-import") (part "R-US_R1206"))
    )
    (comp (ref "R22")
      (value "100R")
      (footprint "eagle-import:R1206")
      (libsource (lib "eagle-import") (part "R-US_R1206"))
    )
    (comp (ref "R23")
      (value "20K")
      (footprint "eagle-import:R1206")
      (libsource (lib "eagle-import") (part "R-US_R1206"))
    )
    (comp (ref "R24")
      (value "510R")
      (footprint "eagle-import:R1206")
      (libsource (lib "eagle-import") (part "R-US_R1206"))
    )
    (comp (ref "R25")
      (value "1K")
      (footprint "eagle-import:R1206")
      (libsource (lib "eagle-import") (part "R-US_R1206"))
    )
    (comp (ref "R26")
      (value "100R")
      (footprint "eagle-import:R1206")
      (libsource (lib "eagle-import") (part "R-US_R1206"))
    )
    (comp (ref "R27")
      (value "100R")
      (footprint "eagle-import:R1206")
      (libsource (lib "eagle-import") (part "R-US_R1206"))
    )
    (comp (ref "R28")
      (value "100R")
      (footprint "eagle-import:R1206")
      (libsource (lib "eagle-import") (part "R-US_R1206"))
    )
    (comp (ref "R29")
      (value "100R")
      (footprint "eagle-import:R1206")
      (libsource (lib "eagle-import") (part "R-US_R1206"))
    )
    (comp (ref "R30")
      (value "100K")
      (footprint "eagle-import:R1206")
      (libsource (lib "eagle-import") (part "R-US_R1206"))
    )
    (comp (ref "R31")
      (value "510R")
      (footprint "eagle-import:R1206")
      (libsource (lib "eagle-import") (part "R-US_R1206"))
    )
    (comp (ref "R32")
      (value "510R")
      (footprint "eagle-import:R1206")
      (libsource (lib "eagle-import") (part "R-US_R1206"))
    )
    (comp (ref "R33")
      (value "510R")
      (footprint "eagle-import:R1206")
      (libsource (lib "eagle-import") (part "R-US_R1206"))
    )
    (comp (ref "R34")
      (value "25R")
      (footprint "eagle-import:R1206")
      (libsource (lib "eagle-import") (part "R-US_R1206"))
    )
    (comp (ref "R35")
      (value "25R")
      (footprint "eagle-import:R1206")
      (libsource (lib "eagle-import") (part "R-US_R1206"))
    )
    (comp (ref "R36")
      (value "10K")
      (footprint "eagle-import:R1206")
      (libsource (lib "eagle-import") (part "R-US_R1206"))
    )
    (comp (ref "R37")
      (value "5.1K")
      (footprint "eagle-import:R1206")
      (libsource (lib "eagle-import") (part "R-US_R1206"))
    )
    (comp (ref "R38")
      (value "10K")
      (footprint "eagle-import:R1206")
      (libsource (lib "eagle-import") (part "R-US_R1206"))
    )
    (comp (ref "R39")
      (value "75R")
      (footprint "eagle-import:R1206")
      (libsource (lib "eagle-import") (part "R-US_R1206"))
    )
    (comp (ref "R40")
      (value "4.7K")
      (footprint "eagle-import:R1206")
      (libsource (lib "eagle-import") (part "R-US_R1206"))
    )
    (comp (ref "R41")
      (value "DNP")
      (footprint "eagle-import:R1206")
      (libsource (lib "eagle-import") (part "R-US_R1206"))
    )
    (comp (ref "R42")
      (value "10K")
      (footprint "eagle-import:R1206")
      (libsource (lib "eagle-import") (part "R-US_R1206"))
    )
    (comp (ref "R43")
      (value "510R")
      (footprint "eagle-import:R1206")
      (libsource (lib "eagle-import") (part "R-US_R1206"))
    )
    (comp (ref "R44")
      (value "10K")
      (footprint "eagle-import:R1206")
      (libsource (lib "eagle-import") (part "R-US_R1206"))
    )
    (comp (ref "R45")
      (value "10K")
      (footprint "eagle-import:R1206")
      (libsource (lib "eagle-import") (part "R-US_R1206"))
    )
    (comp (ref "R46")
      (value "62K")
      (footprint "eagle-import:R1206")
      (libsource (lib "eagle-import") (part "R-US_R1206"))
    )
    (comp (ref "R47")
      (value "62K")
      (footprint "eagle-import:R1206")
      (libsource (lib "eagle-import") (part "R-US_R1206"))
    )
    (comp (ref "SW1")
      (value "1825910-6")
      (footprint "eagle-import:SW4_1825910-B_TEC")
      (fields (field (name "COPYRIGHT") "Copyright (C) 2025 Ultra Librarian. All rights reserved."))
      (libsource (lib "eagle-import") (part "1825910-6SW4_1825910-B_TEC"))
    )
    (comp (ref "SW2")
      (value "1825910-6")
      (footprint "eagle-import:SW4_1825910-B_TEC")
      (fields (field (name "COPYRIGHT") "Copyright (C) 2025 Ultra Librarian. All rights reserved."))
      (libsource (lib "eagle-import") (part "1825910-6SW4_1825910-B_TEC"))
    )
    (comp (ref "TP1")
      (value "TH")
      (footprint "eagle-import:SMALL-TH")
      (libsource (lib "eagle-import") (part "TH"))
    )
    (comp (ref "TP2")
      (value "TH")
      (footprint "eagle-import:SMALL-TH")
      (libsource (lib "eagle-import") (part "TH"))
    )
    (comp (ref "TP3")
      (value "TH")
      (footprint "eagle-import:SMALL-TH")
      (libsource (lib "eagle-import") (part "TH"))
    )
    (comp (ref "TP4")
      (value "TH")
      (footprint "eagle-import:SMALL-TH")
      (libsource (lib "eagle-import") (part "TH"))
    )
    (comp (ref "TP5")
      (value "TH")
      (footprint "eagle-import:SMALL-TH")
      (libsource (lib "eagle-import") (part "TH"))
    )
    (comp (ref "TP6")
      (value "TH")
      (footprint "eagle-import:SMALL-TH")
      (libsource (lib "eagle-import") (part "TH"))
    )
    (comp (ref "TP7")
      (value "TH")
      (footprint "eagle-import:SMALL-TH")
      (libsource (lib "eagle-import") (part "TH"))
    )
    (comp (ref "TP8")
      (value "TH")
      (footprint "eagle-import:SMALL-TH")
      (libsource (lib "eagle-import") (part "TH"))
    )
    (comp (ref "TP9")
      (value "TH")
      (footprint "eagle-import:SMALL-TH")
      (libsource (lib "eagle-import") (part "TH"))
    )
    (comp (ref "TP10")
      (value "TH")
      (footprint "eagle-import:SMALL-TH")
      (libsource (lib "eagle-import") (part "TH"))
    )
    (comp (ref "TP11")
      (value "TH")
      (footprint "eagle-import:SMALL-TH")
      (libsource (lib "eagle-import") (part "TH"))
    )
    (comp (ref "TP12")
      (value "TH")
      (footprint "eagle-import:SMALL-TH")
      (libsource (lib "eagle-import") (part "TH"))
    )
    (comp (ref "TP13")
      (value "TH")
      (footprint "eagle-import:SMALL-TH")
      (libsource (lib "eagle-import") (part "TH"))
    )
    (comp (ref "TP14")
      (value "TH")
      (footprint "eagle-import:SMALL-TH")
      (libsource (lib "eagle-import") (part "TH"))
    )
    (comp (ref "TP15")
      (value "TH")
      (footprint "eagle-import:SMALL-TH")
      (libsource (lib "eagle-import") (part "TH"))
    )
    (comp (ref "TP16")
      (value "TH")
      (footprint "eagle-import:SMALL-TH")
      (libsource (lib "eagle-import") (part "TH"))
    )
    (comp (ref "TP17")
      (value "TH")
      (footprint "eagle-import:SMALL-TH")
      (libsource (lib "eagle-import") (part "TH"))
    )
    (comp (ref "TP18")
      (value "TH")
      (footprint "eagle-import:SMALL-TH")
      (libsource (lib "eagle-import") (part "TH"))
    )
    (comp (ref "TP19")
      (value "TH")
      (footprint "eagle-import:SMALL-TH")
      (libsource (lib "eagle-import") (part "TH"))
    )
    (comp (ref "TP20")
      (value "TH")
      (footprint "eagle-import:SMALL-TH")
      (libsource (lib "eagle-import") (part "TH"))
    )
    (comp (ref "TP21")
      (value "TH")
      (footprint "eagle-import:SMALL-TH")
      (libsource (lib "eagle-import") (part "TH"))
    )
    (comp (ref "TP22")
      (value "TH")
      (footprint "eagle-import:SMALL-TH")
      (libsource (lib "eagle-import") (part "TH"))
    )
    (comp (ref "TP23")
      (value "TH")
      (footprint "eagle-import:SMALL-TH")
      (libsource (lib "eagle-import") (part "TH"))
    )
    (comp (ref "TP24")
      (value "TH")
      (footprint "eagle-import:SMALL-TH")
      (libsource (lib "eagle-import") (part "TH"))
    )
    (comp (ref "TP25")
      (value "TH")
      (footprint "eagle-import:SMALL-TH")
      (libsource (lib "eagle-import") (part "TH"))
    )
    (comp (ref "TP38")
      (value "TH")
      (footprint "eagle-import:SMALL-TH")
      (libsource (lib "eagle-import") (part "TH"))
    )
    (comp (ref "TP39")
      (value "TH")
      (footprint "eagle-import:SMALL-TH")
      (libsource (lib "eagle-import") (part "TH"))
    )
    (comp (ref "TP42")
      (value "TH")
      (footprint "eagle-import:SMALL-TH")
      (libsource (lib "eagle-import") (part "TH"))
    )
    (comp (ref "TP43")
      (value "TH")
      (footprint "eagle-import:SMALL-TH")
      (libsource (lib "eagle-import") (part "TH"))
    )
    (comp (ref "U$1")
      (value "SPAN02C-05")
      (footprint "eagle-import:SPBW03G-12")
      (libsource (lib "eagle-import") (part "MEANWELLSPBW03G-12"))
    )
    (comp (ref "U1")
      (value "R-78K5.0-0.5")
      (footprint "eagle-import:SIP3_R-78K-0.5_RCP")
      (fields (field (name "COPYRIGHT") "Copyright (C) 2025 Ultra Librarian. All rights reserved."))
      (libsource (lib "eagle-import") (part "R-78K5.0-0.5SIP3_R-78K-0.5_RCP"))
    )
    (comp (ref "U2")
      (value "1769205241")
      (footprint "eagle-import:WPME-FISM_SMT-8_L13.2W11.4H7.25")
      (libsource (lib "eagle-import") (part "WPME-FISM_SMT-8_L13.2W11.4H7.25_1769205241"))
    )
    (comp (ref "U3")
      (value "SM712.TCT")
      (footprint "eagle-import:SOT23_SEM-M")
      (fields (field (name "COPYRIGHT") "Copyright (C) 2024 Ultra Librarian. All rights reserved."))
      (libsource (lib "eagle-import") (part "SM712.TCTSOT23_SEM-M"))
    )
    (comp (ref "U4")
      (value "TPS1H200AQDGNRQ1")
      (footprint "eagle-import:SOP65P490X110-9N")
      (fields (field (name "MF") "Texas Instruments"))
      (libsource (lib "eagle-import") (part "TPS1H200AQDGNRQ1"))
    )
    (comp (ref "U5")
      (value "1769205241")
      (footprint "eagle-import:WPME-FISM_SMT-8_L13.2W11.4H7.25")
      (libsource (lib "eagle-import") (part "WPME-FISM_SMT-8_L13.2W11.4H7.25_1769205241"))
    )
    (comp (ref "U6")
      (value "TPS1H200AQDGNRQ1")
      (footprint "eagle-import:SOP65P490X110-9N")
      (fields (field (name "MF") "Texas Instruments"))
      (libsource (lib "eagle-import") (part "TPS1H200AQDGNRQ1"))
    )
    (comp (ref "U7")
      (value "TPS1H200AQDGNRQ1")
      (footprint "eagle-import:SOP65P490X110-9N")
      (fields (field (name "MF") "Texas Instruments"))
      (libsource (lib "eagle-import") (part "TPS1H200AQDGNRQ1"))
    )
    (comp (ref "U8")
      (value "MAX22026FAWA+")
      (footprint "eagle-import:21-0262_W8MS+1_ADI-M")
      (fields (field (name "COPYRIGHT") "Copyright (C) 2024 Ultra Librarian. All rights reserved."))
      (libsource (lib "eagle-import") (part "MAX22026FAWA+21-0262_W8MS+1_ADI-M"))
    )
    (comp (ref "U9")
      (value "TPS1H200AQDGNRQ1")
      (footprint "eagle-import:SOP65P490X110-9N")
      (fields (field (name "MF") "Texas Instruments"))
      (libsource (lib "eagle-import") (part "TPS1H200AQDGNRQ1"))
    )
    (comp (ref "U10")
      (value "HDC3022QDEJRQ1")
      (footprint "eagle-import:WSON8_DEJ_TEX-M")
      (fields (field (name "COPYRIGHT") "Copyright (C) 2025 Ultra Librarian. All rights reserved."))
      (libsource (lib "eagle-import") (part "HDC3022QDEJRQ1WSON8_DEJ_TEX-M"))
    )
    (comp (ref "U11")
      (value "ISO7742DWR")
      (footprint "eagle-import:DW0016B_HV")
      (fields (field (name "COPYRIGHT") "Copyright (C) 2024 Ultra Librarian. All rights reserved."))
      (libsource (lib "eagle-import") (part "ISO7742DWRDW0016B_HV"))
    )
    (comp (ref "U12")
      (value "ISO7742DWR")
      (footprint "eagle-import:DW0016B_HV")
      (fields (field (name "COPYRIGHT") "Copyright (C) 2024 Ultra Librarian. All rights reserved."))
      (libsource (lib "eagle-import") (part "ISO7742DWRDW0016B_HV"))
    )
    (comp (ref "U13")
      (value "ISO7740DWR")
      (footprint "eagle-import:DW0016B_HV")
      (fields (field (name "COPYRIGHT") "Copyright (C) 2024 Ultra Librarian. All rights reserved."))
      (libsource (lib "eagle-import") (part "ISO7740DWRDW0016B_HV"))
    )
    (comp (ref "U14")
      (value "MAX7320AEE+")
      (footprint "eagle-import:21-0055H_16_MXM-M")
      (fields
        (field (name "MANUFACTURER_PART_NUMBER") "MAX7320AEE+T")
        (field (name "COPYRIGHT") "Copyright (C) 2025 Ultra Librarian. All rights reserved.")
      )
      (libsource (lib "eagle-import") (part "MAX7320AEE+T21-0055H_16_MXM-M"))
    )
    (comp (ref "U15")
      (value "R-78K5.0-0.5")
      (footprint "eagle-import:SIP3_R-78K-0.5_RCP")
      (fields (field (name "COPYRIGHT") "Copyright (C) 2025 Ultra Librarian. All rights reserved."))
      (libsource (lib "eagle-import") (part "R-78K5.0-0.5SIP3_R-78K-0.5_RCP"))
    )
    (comp (ref "U16")
      (value "TPS1H200AQDGNRQ1")
      (footprint "eagle-import:SOP65P490X110-9N")
      (fields (field (name "MF") "Texas Instruments"))
      (libsource (lib "eagle-import") (part "TPS1H200AQDGNRQ1"))
    )
    (comp (ref "U17")
      (value "R-78K5.0-0.5")
      (footprint "eagle-import:SIP3_R-78K-0.5_RCP")
      (fields (field (name "COPYRIGHT") "Copyright (C) 2025 Ultra Librarian. All rights reserved."))
      (libsource (lib "eagle-import") (part "R-78K5.0-0.5SIP3_R-78K-0.5_RCP"))
    )
    (comp (ref "U18")
      (value "AT24CM02-SSHD-B")
      (footprint "eagle-import:SOIC8_4P9X3P9MC_MCH-L")
      (fields (field (name "COPYRIGHT") "Copyright (C) 2025 Ultra Librarian. All rights reserved."))
      (libsource (lib "eagle-import") (part "AT24CM02-SSHD-BSOIC8_4P9X3P9MC_MCH-L"))
    )
    (comp (ref "U19")
      (value "PKU4913DPIHS")
      (footprint "eagle-import:PKU4913DPIHS_FPM")
      (fields (field (name "COPYRIGHT") "Copyright (C) 2025 Ultra Librarian. All rights reserved."))
      (libsource (lib "eagle-import") (part "PKU4913DPIHSPKU4913DPIHS_FPM"))
    )
    (comp (ref "U20")
      (value "SKA60C-12")
      (footprint "eagle-import:SKA60_MWU")
      (fields (field (name "COPYRIGHT") "Copyright (C) 2025 Ultra Librarian. All rights reserved."))
      (libsource (lib "eagle-import") (part "SKA60C-12SKA60_MWU"))
    )
    (comp (ref "U21")
      (value "R-78K3.3-2.0")
      (footprint "eagle-import:CONV_R-78K3.3-2.0")
      (fields (field (name "DIGIKEY_PART_NUMBER") "945-R-78K3.3-2.0-ND") (field (name "MF") "Recom Power"))
      (libsource (lib "eagle-import") (part "R-78K3.3-2.0"))
    )
    (comp (ref "U22")
      (value "TXU0104PWR")
      (footprint "eagle-import:TSSOP_0104PWR_TEX-L")
      (fields (field (name "COPYRIGHT") "Copyright (C) 2025 Ultra Librarian. All rights reserved."))
      (libsource (lib "eagle-import") (part "TXU0104PWRTSSOP_0104PWR_TEX-L"))
    )
    (comp (ref "U23")
      (value "PCA9632TK,118")
      (footprint "eagle-import:HVSON8_3X3_NXP")
      (fields (field (name "COPYRIGHT") "Copyright (C) 2025 Ultra Librarian. All rights reserved."))
      (libsource (lib "eagle-import") (part "PCA9632TK,118HVSON8_3X3_NXP"))
    )
    (comp (ref "U24")
      (value "TXU0101DCKRSC70-6_DCK_TEX-L")
      (footprint "eagle-import:SC70-6_DCK_TEX-L")
      (fields
        (field (name "MANUFACTURER_PART_NUMBER") "TXU0101DCKR")
        (field (name "COPYRIGHT") "Copyright (C) 2025 Ultra Librarian. All rights reserved.")
      )
      (libsource (lib "eagle-import") (part "TXU0101DCKRSC70-6_DCK_TEX-L"))
    )
  )
  (nets
    (net (code "1") (name "+5V") (class "Default")
      (node (ref "B1") (pin "P9.5") (pinfunction "VDD_5V_P9.5") (pintype "bidirectional"))
      (node (ref "B1") (pin "P9.6") (pinfunction "VDD_5V_P9.6") (pintype "bidirectional"))
      (node (ref "CR7") (pin "1") (pinfunction "CATHODE_1") (pintype "passive"))
      (node (ref "J2") (pin "4") (pinfunction "4_4") (pintype "passive"))
      (node (ref "PS3") (pin "6") (pinfunction "+VOUT_6") (pintype "power_in"))
      (node (ref "R12") (pin "1") (pinfunction "1_1") (pintype "passive"))
      (node (ref "R3") (pin "1") (pinfunction "1_1") (pintype "passive"))
      (node (ref "R30") (pin "1") (pinfunction "1_1") (pintype "passive"))
      (node (ref "R4") (pin "1") (pinfunction "1_1") (pintype "passive"))
      (node (ref "R8") (pin "1") (pinfunction "1_1") (pintype "passive"))
      (node (ref "U16") (pin "8") (pinfunction "VS_8") (pintype "power_in"))
      (node (ref "U21") (pin "1") (pinfunction "+VIN_1") (pintype "input"))
      (node (ref "U22") (pin "14") (pinfunction "VCCB_14") (pintype "power_in"))
      (node (ref "U22") (pin "8") (pinfunction "OE_8") (pintype "passive"))
      (node (ref "U24") (pin "5") (pinfunction "OE_5") (pintype "input"))
      (node (ref "U24") (pin "6") (pinfunction "VCCB_6") (pintype "power_in"))
      (node (ref "U4") (pin "8") (pinfunction "VS_8") (pintype "power_in"))
      (node (ref "U6") (pin "8") (pinfunction "VS_8") (pintype "power_in"))
      (node (ref "U7") (pin "8") (pinfunction "VS_8") (pintype "power_in"))
      (node (ref "U9") (pin "8") (pinfunction "VS_8") (pintype "power_in"))
    )
    (net (code "2") (name "+5V{slash}3") (class "Default")
      (node (ref "C13") (pin "1") (pinfunction "1_1") (pintype "passive"))
      (node (ref "C14") (pin "1") (pinfunction "1_1") (pintype "passive"))
      (node (ref "CR10") (pin "1") (pinfunction "CATHODE_1") (pintype "passive"))
      (node (ref "R37") (pin "1") (pinfunction "1_1") (pintype "passive"))
      (node (ref "TP19") (pin "P$1") (pinfunction "TP_P$1") (pintype "input"))
      (node (ref "U5") (pin "5") (pinfunction "+VOUT_5") (pintype "output"))
      (node (ref "U8") (pin "8") (pinfunction "VDDB_8") (pintype "power_in"))
    )
    (net (code "3") (name "+12V") (class "Default")
      (node (ref "C18") (pin "+") (pinfunction "+_+") (pintype "passive"))
      (node (ref "C21") (pin "+") (pinfunction "+_+") (pintype "passive"))
      (node (ref "CR13") (pin "1") (pinfunction "CATHODE_1") (pintype "passive"))
      (node (ref "CR8") (pin "1") (pinfunction "CATHODE_1") (pintype "passive"))
      (node (ref "D13") (pin "1") (pinfunction "1_1") (pintype "passive"))
      (node (ref "IC1") (pin "10") (pinfunction "VIN4_10") (pintype "bidirectional"))
      (node (ref "IC1") (pin "11") (pinfunction "VIN3_11") (pintype "bidirectional"))
      (node (ref "IC1") (pin "2") (pinfunction "VIN1_2") (pintype "bidirectional"))
      (node (ref "IC1") (pin "3") (pinfunction "VIN2_3") (pintype "bidirectional"))
      (node (ref "IC3") (pin "10") (pinfunction "VIN4_10") (pintype "bidirectional"))
      (node (ref "IC3") (pin "11") (pinfunction "VIN3_11") (pintype "bidirectional"))
      (node (ref "IC3") (pin "2") (pinfunction "VIN1_2") (pintype "bidirectional"))
      (node (ref "IC3") (pin "3") (pinfunction "VIN2_3") (pintype "bidirectional"))
      (node (ref "J2") (pin "2") (pinfunction "2_2") (pintype "passive"))
      (node (ref "K7") (pin "4") (pinfunction "4_4") (pintype "passive"))
      (node (ref "PS1") (pin "7") (pinfunction "+SENSE_IN_7") (pintype "input"))
      (node (ref "PS1") (pin "8") (pinfunction "+VOUT_8") (pintype "output"))
      (node (ref "TP39") (pin "P$1") (pinfunction "TP_P$1") (pintype "input"))
      (node (ref "U1") (pin "1") (pinfunction "+VIN_1") (pintype "power_in"))
      (node (ref "U19") (pin "8") (pinfunction "+OUT_8") (pintype "output"))
      (node (ref "U2") (pin "2") (pinfunction "+VIN_2") (pintype "input"))
      (node (ref "U20") (pin "5") (pinfunction "+R.S_5") (pintype "passive"))
      (node (ref "U20") (pin "6") (pinfunction "+VOUT_6") (pintype "output"))
      (node (ref "U5") (pin "2") (pinfunction "+VIN_2") (pintype "input"))
    )
    (net (code "4") (name "/12{slash}48VTRIG") (class "Default")
      (node (ref "B1") (pin "P9.12") (pinfunction "GPIO_60_P9.12") (pintype "bidirectional"))
      (node (ref "K6") (pin "2") (pinfunction "2_2") (pintype "passive"))
      (node (ref "R23") (pin "1") (pinfunction "1_1") (pintype "passive"))
    )
    (net (code "5") (name "/BU-REL-C") (class "Default")
      (node (ref "D14") (pin "C") (pinfunction "K_C") (pintype "passive"))
      (node (ref "J8") (pin "3") (pinfunction "3_3") (pintype "passive"))
      (node (ref "K1") (pin "2") (pinfunction "2_2") (pintype "passive"))
    )
    (net (code "6") (name "/EFUSE-EN-2") (class "Default")
      (node (ref "U12") (pin "12") (pinfunction "INC_12") (pintype "input"))
      (node (ref "U14") (pin "10") (pinfunction "O5_10") (pintype "output"))
    )
    (net (code "7") (name "/EFUSE-EN-3") (class "Default")
      (node (ref "U12") (pin "11") (pinfunction "IND_11") (pintype "input"))
      (node (ref "U14") (pin "11") (pinfunction "O6_11") (pintype "output"))
    )
    (net (code "8") (name "/EFUSE-F-1") (class "Default")
      (node (ref "B1") (pin "P9.23") (pinfunction "GPIO_49_P9.23") (pintype "bidirectional"))
      (node (ref "U11") (pin "14") (pinfunction "OUTA_14") (pintype "tri_state"))
    )
    (net (code "9") (name "/EFUSE-F-2") (class "Default")
      (node (ref "B1") (pin "P8.8") (pinfunction "GPIO_67_P8.8") (pintype "bidirectional"))
      (node (ref "U12") (pin "14") (pinfunction "OUTA_14") (pintype "tri_state"))
    )
    (net (code "10") (name "/EFUSE-F-3") (class "Default")
      (node (ref "B1") (pin "P8.12") (pinfunction "GPIO_44_P8.12") (pintype "bidirectional"))
      (node (ref "U12") (pin "13") (pinfunction "OUTB_13") (pintype "tri_state"))
    )
    (net (code "11") (name "/EFUSE_GAS_ON") (class "Default")
      (node (ref "B1") (pin "P9.27") (pinfunction "GPIO_125_P9.27") (pintype "bidirectional"))
      (node (ref "U11") (pin "13") (pinfunction "OUTB_13") (pintype "tri_state"))
    )
    (net (code "12") (name "/EN-AU") (class "Default")
      (node (ref "IC3") (pin "13") (pinfunction "EN4_13") (pintype "bidirectional"))
      (node (ref "IC3") (pin "14") (pinfunction "EN3_14") (pintype "bidirectional"))
      (node (ref "IC3") (pin "15") (pinfunction "EN2_15") (pintype "bidirectional"))
      (node (ref "IC3") (pin "16") (pinfunction "EN1_16") (pintype "bidirectional"))
      (node (ref "U12") (pin "6") (pinfunction "OUTD_6") (pintype "tri_state"))
    )
    (net (code "13") (name "/EN-BU") (class "Default")
      (node (ref "IC1") (pin "13") (pinfunction "EN4_13") (pintype "bidirectional"))
      (node (ref "IC1") (pin "14") (pinfunction "EN3_14") (pintype "bidirectional"))
      (node (ref "IC1") (pin "15") (pinfunction "EN2_15") (pintype "bidirectional"))
      (node (ref "IC1") (pin "16") (pinfunction "EN1_16") (pintype "bidirectional"))
      (node (ref "U12") (pin "5") (pinfunction "OUTC_5") (pintype "tri_state"))
    )
    (net (code "14") (name "/F-AU") (class "Default")
      (node (ref "IC3") (pin "5") (pinfunction "FAULT_5") (pintype "bidirectional"))
      (node (ref "R11") (pin "2") (pinfunction "2_2") (pintype "passive"))
      (node (ref "U12") (pin "4") (pinfunction "INB_4") (pintype "input"))
    )
    (net (code "15") (name "/F-BU") (class "Default")
      (node (ref "IC1") (pin "5") (pinfunction "FAULT_5") (pintype "bidirectional"))
      (node (ref "R9") (pin "2") (pinfunction "2_2") (pintype "passive"))
      (node (ref "U12") (pin "3") (pinfunction "INA_3") (pintype "input"))
    )
    (net (code "16") (name "/FAULT-1") (class "Default")
      (node (ref "R20") (pin "2") (pinfunction "2_2") (pintype "passive"))
      (node (ref "U11") (pin "3") (pinfunction "INA_3") (pintype "input"))
      (node (ref "U17") (pin "3") (pinfunction "+VOUT_3") (pintype "output"))
    )
    (net (code "17") (name "/GAS-12V-5V") (class "Default")
      (node (ref "C1") (pin "1") (pinfunction "1_1") (pintype "passive"))
      (node (ref "CR11") (pin "1") (pinfunction "CATHODE_1") (pintype "passive"))
      (node (ref "TP18") (pin "P$1") (pinfunction "TP_P$1") (pintype "input"))
      (node (ref "U11") (pin "1") (pinfunction "VCC1_1") (pintype "power_in"))
      (node (ref "U11") (pin "7") (pinfunction "EN1_7") (pintype "input"))
      (node (ref "U2") (pin "5") (pinfunction "+VOUT_5") (pintype "output"))
    )
    (net (code "18") (name "/GAS-12V-GND") (class "Default")
      (node (ref "C1") (pin "2") (pinfunction "2_2") (pintype "passive"))
      (node (ref "CR11") (pin "2") (pinfunction "ANODE_2") (pintype "passive"))
      (node (ref "CR5") (pin "2") (pinfunction "ANODE_2") (pintype "passive"))
      (node (ref "CR6") (pin "2") (pinfunction "ANODE_2") (pintype "passive"))
      (node (ref "J4") (pin "2") (pinfunction "2_2") (pintype "passive"))
      (node (ref "K7") (pin "6") (pinfunction "6_6") (pintype "passive"))
      (node (ref "R19") (pin "1") (pinfunction "1_1") (pintype "passive"))
      (node (ref "R20") (pin "1") (pinfunction "1_1") (pintype "passive"))
      (node (ref "TP21") (pin "P$1") (pinfunction "TP_P$1") (pintype "input"))
      (node (ref "U11") (pin "2") (pinfunction "GND1_2_2") (pintype "power_in"))
      (node (ref "U11") (pin "8") (pinfunction "GND1_8") (pintype "power_in"))
      (node (ref "U15") (pin "2") (pinfunction "GND_2") (pintype "passive"))
      (node (ref "U17") (pin "2") (pinfunction "GND_2") (pintype "passive"))
      (node (ref "U2") (pin "4") (pinfunction "-VOUT_4") (pintype "output"))
    )
    (net (code "19") (name "/GAS-12V-POS") (class "Default")
      (node (ref "K2") (pin "2") (pinfunction "2_2") (pintype "passive"))
      (node (ref "K7") (pin "3") (pinfunction "3_3") (pintype "passive"))
    )
    (net (code "20") (name "/GAS-12V-PWR") (class "Default")
      (node (ref "CR5") (pin "1") (pinfunction "CATHODE_1") (pintype "passive"))
      (node (ref "F4") (pin "1") (pinfunction "1_1") (pintype "passive"))
      (node (ref "J4") (pin "1") (pinfunction "1_1") (pintype "passive"))
      (node (ref "U17") (pin "1") (pinfunction "+VIN_1") (pintype "power_in"))
    )
    (net (code "21") (name "/GAS_ON") (class "Default")
      (node (ref "R19") (pin "2") (pinfunction "2_2") (pintype "passive"))
      (node (ref "U11") (pin "4") (pinfunction "INB_4") (pintype "input"))
      (node (ref "U15") (pin "3") (pinfunction "+VOUT_3") (pintype "output"))
    )
    (net (code "22") (name "/INDICATOR1") (class "Default")
      (node (ref "B1") (pin "P8.44") (pinfunction "GPIO_73_P8.44") (pintype "bidirectional"))
      (node (ref "LED5") (pin "A") (pinfunction "A_A") (pintype "passive"))
    )
    (net (code "23") (name "/INDICATOR2") (class "Default")
      (node (ref "B1") (pin "P8.42") (pinfunction "GPIO_75_P8.42") (pintype "bidirectional"))
      (node (ref "LED4") (pin "A") (pinfunction "A_A") (pintype "passive"))
    )
    (net (code "24") (name "/INDICATOR3") (class "Default")
      (node (ref "B1") (pin "P8.46") (pinfunction "GPIO_71_P8.46") (pintype "bidirectional"))
      (node (ref "LED3") (pin "A") (pinfunction "A_A") (pintype "passive"))
    )
    (net (code "25") (name "/INDICATOR4") (class "Default")
      (node (ref "B1") (pin "P8.45") (pinfunction "GPIO_70_P8.45") (pintype "bidirectional"))
      (node (ref "LED2") (pin "A") (pinfunction "A_A") (pintype "passive"))
    )
    (net (code "26") (name "/INPUT1") (class "Default")
      (node (ref "B1") (pin "P8.41") (pinfunction "GPIO_74_P8.41") (pintype "bidirectional"))
      (node (ref "R36") (pin "1") (pinfunction "1_1") (pintype "passive"))
      (node (ref "SW1") (pin "1") (pinfunction "1_1") (pintype "passive"))
      (node (ref "SW1") (pin "2") (pinfunction "2_2") (pintype "passive"))
    )
    (net (code "27") (name "/INPUT2") (class "Default")
      (node (ref "B1") (pin "P8.43") (pinfunction "GPIO_72_P8.43") (pintype "bidirectional"))
      (node (ref "R38") (pin "1") (pinfunction "1_1") (pintype "passive"))
      (node (ref "SW2") (pin "1") (pinfunction "1_1") (pintype "passive"))
      (node (ref "SW2") (pin "2") (pinfunction "2_2") (pintype "passive"))
    )
    (net (code "28") (name "/MEM-WP") (class "Default")
      (node (ref "JP1") (pin "1") (pinfunction "1_1") (pintype "passive"))
      (node (ref "R45") (pin "2") (pinfunction "2_2") (pintype "passive"))
      (node (ref "U18") (pin "7") (pinfunction "WP_7") (pintype "passive"))
    )
    (net (code "29") (name "/MOD-RX") (class "Default")
      (node (ref "B1") (pin "P9.26") (pinfunction "GPIO_14_P9.26") (pintype "bidirectional"))
      (node (ref "U8") (pin "1") (pinfunction "RXD_1") (pintype "output"))
    )
    (net (code "30") (name "/MOD-TX") (class "Default")
      (node (ref "B1") (pin "P9.24") (pinfunction "GPIO_15_P9.24") (pintype "bidirectional"))
      (node (ref "U8") (pin "2") (pinfunction "TXD_2") (pintype "input"))
    )
    (net (code "31") (name "/PB-48V-GND") (class "Default")
      (node (ref "D10") (pin "2") (pinfunction "2_2") (pintype "passive"))
      (node (ref "J18") (pin "1") (pinfunction "1_1") (pintype "passive"))
      (node (ref "J18") (pin "2") (pinfunction "2_2") (pintype "passive"))
      (node (ref "J18") (pin "3") (pinfunction "3_3") (pintype "passive"))
      (node (ref "J5") (pin "4") (pinfunction "4_4") (pintype "passive"))
      (node (ref "K8") (pin "NO2") (pinfunction "NO2_NO2") (pintype "bidirectional"))
      (node (ref "PS1") (pin "2") (pinfunction "ON/OFF_CNTRL_2") (pintype "input"))
      (node (ref "PS1") (pin "3") (pinfunction "-VIN_3") (pintype "input"))
      (node (ref "PS3") (pin "2") (pinfunction "-VIN_2") (pintype "power_in"))
      (node (ref "TP12") (pin "P$1") (pinfunction "TP_P$1") (pintype "input"))
      (node (ref "U19") (pin "2") (pinfunction "RC_2") (pintype "passive"))
      (node (ref "U19") (pin "3") (pinfunction "-IN_3") (pintype "input"))
      (node (ref "U20") (pin "2") (pinfunction "-VIN_2") (pintype "power_in"))
    )
    (net (code "32") (name "/PB-48V-POS") (class "Default")
      (node (ref "D10") (pin "1") (pinfunction "1_1") (pintype "passive"))
      (node (ref "J19") (pin "1") (pinfunction "1_1") (pintype "passive"))
      (node (ref "J19") (pin "2") (pinfunction "2_2") (pintype "passive"))
      (node (ref "J19") (pin "3") (pinfunction "3_3") (pintype "passive"))
      (node (ref "J5") (pin "3") (pinfunction "3_3") (pintype "passive"))
      (node (ref "K8") (pin "NO1") (pinfunction "NO1_NO1") (pintype "bidirectional"))
      (node (ref "PS1") (pin "1") (pinfunction "+VIN_1") (pintype "input"))
      (node (ref "PS3") (pin "1") (pinfunction "+VIN_1") (pintype "power_in"))
      (node (ref "TP15") (pin "P$1") (pinfunction "TP_P$1") (pintype "input"))
      (node (ref "U19") (pin "1") (pinfunction "+IN_1") (pintype "input"))
      (node (ref "U20") (pin "3") (pinfunction "+VIN_3") (pintype "power_in"))
    )
    (net (code "33") (name "/PB-48V{slash}12V-GND") (class "Default")
      (node (ref "D11") (pin "2") (pinfunction "2_2") (pintype "passive"))
      (node (ref "J20") (pin "1") (pinfunction "1_1") (pintype "passive"))
      (node (ref "J20") (pin "2") (pinfunction "2_2") (pintype "passive"))
      (node (ref "J20") (pin "3") (pinfunction "3_3") (pintype "passive"))
      (node (ref "K7") (pin "7") (pinfunction "7_7") (pintype "passive"))
      (node (ref "K8") (pin "COM2") (pinfunction "COM2_COM2") (pintype "bidirectional"))
      (node (ref "TP23") (pin "P$1") (pinfunction "TP_P$1") (pintype "input"))
      (node (ref "U$1") (pin "-VIN") (pinfunction "-VIN_-VIN") (pintype "bidirectional"))
    )
    (net (code "34") (name "/PB-48V{slash}12V-POS") (class "Default")
      (node (ref "D11") (pin "1") (pinfunction "1_1") (pintype "passive"))
      (node (ref "J12") (pin "1") (pinfunction "1_1") (pintype "passive"))
      (node (ref "J12") (pin "2") (pinfunction "2_2") (pintype "passive"))
      (node (ref "J12") (pin "3") (pinfunction "3_3") (pintype "passive"))
      (node (ref "K7") (pin "2") (pinfunction "2_2") (pintype "passive"))
      (node (ref "K8") (pin "COM1") (pinfunction "COM1_COM1") (pintype "bidirectional"))
      (node (ref "TP22") (pin "P$1") (pinfunction "TP_P$1") (pintype "input"))
      (node (ref "U$1") (pin "+VIN") (pinfunction "+VIN_+VIN") (pintype "bidirectional"))
    )
    (net (code "35") (name "/PUSH_BUTTON_IN") (class "Default")
      (node (ref "B1") (pin "P8.10") (pinfunction "GPIO_68_P8.10") (pintype "bidirectional"))
      (node (ref "J6") (pin "6") (pinfunction "6_6") (pintype "passive"))
      (node (ref "R42") (pin "1") (pinfunction "1_1") (pintype "passive"))
    )
    (net (code "36") (name "/PWR-AU") (class "Default")
      (node (ref "C23") (pin "+") (pinfunction "+_+") (pintype "passive"))
      (node (ref "CR14") (pin "1") (pinfunction "CATHODE_1") (pintype "passive"))
      (node (ref "IC3") (pin "1") (pinfunction "VOUT1_1") (pintype "bidirectional"))
      (node (ref "IC3") (pin "12") (pinfunction "VOUT3_12") (pintype "bidirectional"))
      (node (ref "IC3") (pin "4") (pinfunction "VOUT2_4") (pintype "bidirectional"))
      (node (ref "IC3") (pin "9") (pinfunction "VOUT4_9") (pintype "bidirectional"))
      (node (ref "J3") (pin "1") (pinfunction "1_1") (pintype "passive"))
    )
    (net (code "37") (name "/PWR-BU") (class "Default")
      (node (ref "C20") (pin "+") (pinfunction "+_+") (pintype "passive"))
      (node (ref "CR9") (pin "1") (pinfunction "CATHODE_1") (pintype "passive"))
      (node (ref "IC1") (pin "1") (pinfunction "VOUT1_1") (pintype "bidirectional"))
      (node (ref "IC1") (pin "12") (pinfunction "VOUT3_12") (pintype "bidirectional"))
      (node (ref "IC1") (pin "4") (pinfunction "VOUT2_4") (pintype "bidirectional"))
      (node (ref "IC1") (pin "9") (pinfunction "VOUT4_9") (pintype "bidirectional"))
      (node (ref "J8") (pin "1") (pinfunction "1_1") (pintype "passive"))
      (node (ref "K1") (pin "3") (pinfunction "3_3") (pintype "passive"))
    )
    (net (code "38") (name "/R1W1") (class "Default")
      (node (ref "B1") (pin "P8.14") (pinfunction "GPIO_26_P8.14") (pintype "bidirectional"))
      (node (ref "B1") (pin "P8.15") (pinfunction "GPIO_47_P8.15") (pintype "bidirectional"))
      (node (ref "U13") (pin "11") (pinfunction "OUTD_11") (pintype "tri_state"))
    )
    (net (code "39") (name "/R1W2") (class "Default")
      (node (ref "B1") (pin "P8.16") (pinfunction "GPIO_46_P8.16") (pintype "bidirectional"))
      (node (ref "U13") (pin "12") (pinfunction "OUTC_12") (pintype "tri_state"))
    )
    (net (code "40") (name "/R2W1") (class "Default")
      (node (ref "B1") (pin "P8.18") (pinfunction "GPIO_65_P8.18") (pintype "bidirectional"))
      (node (ref "B1") (pin "P8.40") (pinfunction "GPIO_77_P8.40") (pintype "bidirectional"))
      (node (ref "U13") (pin "13") (pinfunction "OUTB_13") (pintype "tri_state"))
    )
    (net (code "41") (name "/R2W2") (class "Default")
      (node (ref "B1") (pin "P8.26") (pinfunction "GPIO_61_P8.26") (pintype "bidirectional"))
      (node (ref "B1") (pin "P8.39") (pinfunction "GPIO_76_P8.39") (pintype "bidirectional"))
      (node (ref "U13") (pin "14") (pinfunction "OUTA_14") (pintype "tri_state"))
    )
    (net (code "42") (name "/RELAY1") (class "Default")
      (node (ref "U14") (pin "4") (pinfunction "O0_4") (pintype "output"))
      (node (ref "U22") (pin "5") (pinfunction "A4_5") (pintype "bidirectional"))
    )
    (net (code "43") (name "/RELAY1SU") (class "Default")
      (node (ref "U22") (pin "10") (pinfunction "B4Y_10") (pintype "bidirectional"))
      (node (ref "U9") (pin "1") (pinfunction "IN_1") (pintype "input"))
      (node (ref "U9") (pin "2") (pinfunction "DIAG_EN_2") (pintype "input"))
    )
    (net (code "44") (name "/RELAY2") (class "Default")
      (node (ref "U14") (pin "5") (pinfunction "O1_5") (pintype "output"))
      (node (ref "U22") (pin "4") (pinfunction "A3_4") (pintype "bidirectional"))
    )
    (net (code "45") (name "/RELAY2SU") (class "Default")
      (node (ref "U22") (pin "11") (pinfunction "B3Y_11") (pintype "bidirectional"))
      (node (ref "U4") (pin "1") (pinfunction "IN_1") (pintype "input"))
      (node (ref "U4") (pin "2") (pinfunction "DIAG_EN_2") (pintype "input"))
    )
    (net (code "46") (name "/RELAY3") (class "Default")
      (node (ref "U14") (pin "6") (pinfunction "O2_6") (pintype "output"))
      (node (ref "U22") (pin "3") (pinfunction "A2_3") (pintype "bidirectional"))
    )
    (net (code "47") (name "/RELAY3SU") (class "Default")
      (node (ref "U22") (pin "12") (pinfunction "B2Y_12") (pintype "bidirectional"))
      (node (ref "U6") (pin "1") (pinfunction "IN_1") (pintype "input"))
      (node (ref "U6") (pin "2") (pinfunction "DIAG_EN_2") (pintype "input"))
    )
    (net (code "48") (name "/RELAY4") (class "Default")
      (node (ref "U14") (pin "7") (pinfunction "O3_7") (pintype "output"))
      (node (ref "U22") (pin "2") (pinfunction "A1_2") (pintype "bidirectional"))
    )
    (net (code "49") (name "/RELAY4SU") (class "Default")
      (node (ref "U22") (pin "13") (pinfunction "B1Y_13") (pintype "bidirectional"))
      (node (ref "U7") (pin "1") (pinfunction "IN_1") (pintype "input"))
      (node (ref "U7") (pin "2") (pinfunction "DIAG_EN_2") (pintype "input"))
    )
    (net (code "50") (name "/RELAY5") (class "Default")
      (node (ref "U14") (pin "12") (pinfunction "O7_12") (pintype "output"))
      (node (ref "U24") (pin "3") (pinfunction "A_3") (pintype "input"))
    )
    (net (code "51") (name "/RELAY5SU") (class "Default")
      (node (ref "U16") (pin "1") (pinfunction "IN_1") (pintype "input"))
      (node (ref "U16") (pin "2") (pinfunction "DIAG_EN_2") (pintype "input"))
      (node (ref "U24") (pin "4") (pinfunction "BY_4") (pintype "output"))
    )
    (net (code "52") (name "/RESET") (class "Default")
      (node (ref "R44") (pin "2") (pinfunction "2_2") (pintype "passive"))
      (node (ref "U14") (pin "2") (pinfunction "~{RST}_2") (pintype "input"))
    )
    (net (code "53") (name "/SCL") (class "Default")
      (node (ref "B1") (pin "P9.19") (pinfunction "I2C2_SCL_P9.19") (pintype "bidirectional"))
      (node (ref "R40") (pin "2") (pinfunction "2_2") (pintype "passive"))
      (node (ref "U10") (pin "4") (pinfunction "SCL_4") (pintype "input"))
      (node (ref "U14") (pin "14") (pinfunction "SCL_14") (pintype "input"))
      (node (ref "U18") (pin "6") (pinfunction "SCL_6") (pintype "passive"))
      (node (ref "U23") (pin "6") (pinfunction "SCL_6") (pintype "passive"))
    )
    (net (code "54") (name "/SDA") (class "Default")
      (node (ref "B1") (pin "P9.20") (pinfunction "I2C2_SDA_P9.20") (pintype "bidirectional"))
      (node (ref "R5") (pin "2") (pinfunction "2_2") (pintype "passive"))
      (node (ref "U10") (pin "1") (pinfunction "SDA_1") (pintype "bidirectional"))
      (node (ref "U14") (pin "15") (pinfunction "SDA_15") (pintype "bidirectional"))
      (node (ref "U18") (pin "5") (pinfunction "SDA_5") (pintype "passive"))
      (node (ref "U23") (pin "7") (pinfunction "SDA_7") (pintype "passive"))
    )
    (net (code "55") (name "GND") (class "Default")
      (node (ref "B1") (pin "P8.1") (pinfunction "DGND_P8.1") (pintype "bidirectional"))
      (node (ref "B1") (pin "P8.2") (pinfunction "DGND_P8.2") (pintype "bidirectional"))
      (node (ref "B1") (pin "P9.1") (pinfunction "DGND_P9.1") (pintype "bidirectional"))
      (node (ref "B1") (pin "P9.2") (pinfunction "DGND_P9.2") (pintype "bidirectional"))
      (node (ref "B1") (pin "P9.43") (pinfunction "DGND_P9.43") (pintype "bidirectional"))
      (node (ref "B1") (pin "P9.44") (pinfunction "DGND_P9.44") (pintype "bidirectional"))
      (node (ref "B1") (pin "P9.45") (pinfunction "DGND_P9.45") (pintype "bidirectional"))
      (node (ref "B1") (pin "P9.46") (pinfunction "DGND_P9.46") (pintype "bidirectional"))
      (node (ref "C10") (pin "2") (pinfunction "2_2") (pintype "passive"))
      (node (ref "C2") (pin "2") (pinfunction "2_2") (pintype "passive"))
      (node (ref "C3") (pin "2") (pinfunction "2_2") (pintype "passive"))
      (node (ref "C6") (pin "2") (pinfunction "2_2") (pintype "passive"))
      (node (ref "C7") (pin "2") (pinfunction "2_2") (pintype "passive"))
      (node (ref "C8") (pin "2") (pinfunction "2_2") (pintype "passive"))
      (node (ref "C9") (pin "2") (pinfunction "2_2") (pintype "passive"))
      (node (ref "CR15") (pin "2") (pinfunction "ANODE_2") (pintype "passive"))
      (node (ref "CR7") (pin "2") (pinfunction "ANODE_2") (pintype "passive"))
      (node (ref "D1") (pin "A") (pinfunction "A_A") (pintype "passive"))
      (node (ref "D2") (pin "A") (pinfunction "A_A") (pintype "passive"))
      (node (ref "D3") (pin "A") (pinfunction "A_A") (pintype "passive"))
      (node (ref "D4") (pin "A") (pinfunction "A_A") (pintype "passive"))
      (node (ref "D5") (pin "A") (pinfunction "A_A") (pintype "passive"))
      (node (ref "J2") (pin "3") (pinfunction "3_3") (pintype "passive"))
      (node (ref "J6") (pin "7") (pinfunction "7_7") (pintype "passive"))
      (node (ref "J6") (pin "8") (pinfunction "8_8") (pintype "passive"))
      (node (ref "JP1") (pin "2") (pinfunction "2_2") (pintype "passive"))
      (node (ref "K1") (pin "1") (pinfunction "1_1") (pintype "passive"))
      (node (ref "K2") (pin "1") (pinfunction "1_1") (pintype "passive"))
      (node (ref "K3") (pin "1") (pinfunction "1_1") (pintype "passive"))
      (node (ref "K4") (pin "1") (pinfunction "1_1") (pintype "passive"))
      (node (ref "K5") (pin "1") (pinfunction "1_1") (pintype "passive"))
      (node (ref "K6") (pin "3") (pinfunction "3_3") (pintype "passive"))
      (node (ref "PS3") (pin "4") (pinfunction "-VOUT_4") (pintype "power_in"))
      (node (ref "R1") (pin "2") (pinfunction "2_2") (pintype "passive"))
      (node (ref "R10") (pin "2") (pinfunction "2_2") (pintype "passive"))
      (node (ref "R2") (pin "2") (pinfunction "2_2") (pintype "passive"))
      (node (ref "R24") (pin "2") (pinfunction "2_2") (pintype "passive"))
      (node (ref "R25") (pin "2") (pinfunction "2_2") (pintype "passive"))
      (node (ref "R31") (pin "2") (pinfunction "2_2") (pintype "passive"))
      (node (ref "R32") (pin "2") (pinfunction "2_2") (pintype "passive"))
      (node (ref "R33") (pin "2") (pinfunction "2_2") (pintype "passive"))
      (node (ref "R43") (pin "2") (pinfunction "2_2") (pintype "passive"))
      (node (ref "R7") (pin "2") (pinfunction "2_2") (pintype "passive"))
      (node (ref "SW1") (pin "3") (pinfunction "3_3") (pintype "passive"))
      (node (ref "SW1") (pin "4") (pinfunction "4_4") (pintype "passive"))
      (node (ref "SW2") (pin "3") (pinfunction "3_3") (pintype "passive"))
      (node (ref "SW2") (pin "4") (pinfunction "4_4") (pintype "passive"))
      (node (ref "TP24") (pin "P$1") (pinfunction "TP_P$1") (pintype "input"))
      (node (ref "U10") (pin "8") (pinfunction "GND_8") (pintype "passive"))
      (node (ref "U11") (pin "15") (pinfunction "GND2_15") (pintype "power_in"))
      (node (ref "U11") (pin "9") (pinfunction "GND2_2_9") (pintype "power_in"))
      (node (ref "U12") (pin "15") (pinfunction "GND2_15") (pintype "power_in"))
      (node (ref "U12") (pin "9") (pinfunction "GND2_2_9") (pintype "power_in"))
      (node (ref "U13") (pin "15") (pinfunction "GND2_15") (pintype "power_in"))
      (node (ref "U13") (pin "9") (pinfunction "GND2_2_9") (pintype "power_in"))
      (node (ref "U14") (pin "1") (pinfunction "AD0_1") (pintype "input"))
      (node (ref "U14") (pin "3") (pinfunction "AD2_3") (pintype "input"))
      (node (ref "U14") (pin "8") (pinfunction "GND_8") (pintype "power_in"))
      (node (ref "U16") (pin "6") (pinfunction "GND_6") (pintype "power_in"))
      (node (ref "U16") (pin "9") (pinfunction "EP_9") (pintype "bidirectional"))
      (node (ref "U18") (pin "3") (pinfunction "A2_3") (pintype "passive"))
      (node (ref "U18") (pin "4") (pinfunction "GND_4") (pintype "passive"))
      (node (ref "U21") (pin "2") (pinfunction "GND_2") (pintype "power_in"))
      (node (ref "U22") (pin "7") (pinfunction "GND_7") (pintype "passive"))
      (node (ref "U23") (pin "5") (pinfunction "VSS_5") (pintype "passive"))
      (node (ref "U24") (pin "2") (pinfunction "GND_2") (pintype "passive"))
      (node (ref "U4") (pin "6") (pinfunction "GND_6") (pintype "power_in"))
      (node (ref "U4") (pin "9") (pinfunction "EP_9") (pintype "bidirectional"))
      (node (ref "U6") (pin "6") (pinfunction "GND_6") (pintype "power_in"))
      (node (ref "U6") (pin "9") (pinfunction "EP_9") (pintype "bidirectional"))
      (node (ref "U7") (pin "6") (pinfunction "GND_6") (pintype "power_in"))
      (node (ref "U7") (pin "9") (pinfunction "EP_9") (pintype "bidirectional"))
      (node (ref "U8") (pin "4") (pinfunction "GNDA_4") (pintype "passive"))
      (node (ref "U9") (pin "6") (pinfunction "GND_6") (pintype "power_in"))
      (node (ref "U9") (pin "9") (pinfunction "EP_9") (pintype "bidirectional"))
    )
    (net (code "56") (name "GND2") (class "Default")
      (node (ref "D12") (pin "2") (pinfunction "2_2") (pintype "passive"))
      (node (ref "J5") (pin "2") (pinfunction "2_2") (pintype "passive"))
      (node (ref "J7") (pin "1") (pinfunction "1_1") (pintype "passive"))
      (node (ref "TP43") (pin "P$1") (pinfunction "TP_P$1") (pintype "input"))
    )
    (net (code "57") (name "GND3") (class "Default")
      (node (ref "C13") (pin "2") (pinfunction "2_2") (pintype "passive"))
      (node (ref "C14") (pin "2") (pinfunction "2_2") (pintype "passive"))
      (node (ref "CR10") (pin "2") (pinfunction "ANODE_2") (pintype "passive"))
      (node (ref "R16") (pin "2") (pinfunction "2_2") (pintype "passive"))
      (node (ref "TP20") (pin "P$1") (pinfunction "TP_P$1") (pintype "input"))
      (node (ref "U3") (pin "3") (pinfunction "3_3") (pintype "passive"))
      (node (ref "U5") (pin "4") (pinfunction "-VOUT_4") (pintype "output"))
      (node (ref "U8") (pin "5") (pinfunction "GNDB_5") (pintype "passive"))
    )
    (net (code "58") (name "GND4") (class "Default")
      (node (ref "C18") (pin "-") (pinfunction "-_-") (pintype "passive"))
      (node (ref "C19") (pin "2") (pinfunction "2_2") (pintype "passive"))
      (node (ref "C20") (pin "-") (pinfunction "-_-") (pintype "passive"))
      (node (ref "C21") (pin "-") (pinfunction "-_-") (pintype "passive"))
      (node (ref "C22") (pin "2") (pinfunction "2_2") (pintype "passive"))
      (node (ref "C23") (pin "-") (pinfunction "-_-") (pintype "passive"))
      (node (ref "C4") (pin "2") (pinfunction "2_2") (pintype "passive"))
      (node (ref "C5") (pin "2") (pinfunction "2_2") (pintype "passive"))
      (node (ref "CR1") (pin "2") (pinfunction "ANODE_2") (pintype "passive"))
      (node (ref "CR12") (pin "2") (pinfunction "ANODE_2") (pintype "passive"))
      (node (ref "CR13") (pin "2") (pinfunction "ANODE_2") (pintype "passive"))
      (node (ref "CR14") (pin "2") (pinfunction "ANODE_2") (pintype "passive"))
      (node (ref "CR2") (pin "2") (pinfunction "ANODE_2") (pintype "passive"))
      (node (ref "CR3") (pin "2") (pinfunction "ANODE_2") (pintype "passive"))
      (node (ref "CR4") (pin "2") (pinfunction "ANODE_2") (pintype "passive"))
      (node (ref "CR8") (pin "2") (pinfunction "ANODE_2") (pintype "passive"))
      (node (ref "CR9") (pin "2") (pinfunction "ANODE_2") (pintype "passive"))
      (node (ref "D13") (pin "2") (pinfunction "2_2") (pintype "passive"))
      (node (ref "D14") (pin "A") (pinfunction "A_A") (pintype "passive"))
      (node (ref "IC1") (pin "17") (pinfunction "GND_2_17") (pintype "bidirectional"))
      (node (ref "IC1") (pin "8") (pinfunction "GND_1_8") (pintype "bidirectional"))
      (node (ref "IC3") (pin "17") (pinfunction "GND_2_17") (pintype "bidirectional"))
      (node (ref "IC3") (pin "8") (pinfunction "GND_1_8") (pintype "bidirectional"))
      (node (ref "J2") (pin "1") (pinfunction "1_1") (pintype "passive"))
      (node (ref "J3") (pin "2") (pinfunction "2_2") (pintype "passive"))
      (node (ref "J8") (pin "2") (pinfunction "2_2") (pintype "passive"))
      (node (ref "K3") (pin "3") (pinfunction "3_3") (pintype "passive"))
      (node (ref "K4") (pin "3") (pinfunction "3_3") (pintype "passive"))
      (node (ref "K5") (pin "3") (pinfunction "3_3") (pintype "passive"))
      (node (ref "K7") (pin "5") (pinfunction "5_5") (pintype "passive"))
      (node (ref "PS1") (pin "4") (pinfunction "-VOUT_4") (pintype "output"))
      (node (ref "PS1") (pin "5") (pinfunction "–SENSE_IN_5") (pintype "input"))
      (node (ref "R46") (pin "1") (pinfunction "1_1") (pintype "passive"))
      (node (ref "R47") (pin "1") (pinfunction "1_1") (pintype "passive"))
      (node (ref "TP11") (pin "P$1") (pinfunction "TP_P$1") (pintype "input"))
      (node (ref "TP38") (pin "P$1") (pinfunction "TP_P$1") (pintype "input"))
      (node (ref "U1") (pin "2") (pinfunction "GND_2") (pintype "passive"))
      (node (ref "U12") (pin "2") (pinfunction "GND1_2_2") (pintype "power_in"))
      (node (ref "U12") (pin "8") (pinfunction "GND1_8") (pintype "power_in"))
      (node (ref "U13") (pin "2") (pinfunction "GND1_2_2") (pintype "power_in"))
      (node (ref "U13") (pin "8") (pinfunction "GND1_8") (pintype "power_in"))
      (node (ref "U19") (pin "4") (pinfunction "-OUT_4") (pintype "output"))
      (node (ref "U2") (pin "1") (pinfunction "-VIN_1") (pintype "input"))
      (node (ref "U20") (pin "4") (pinfunction "-R.S_4") (pintype "passive"))
      (node (ref "U20") (pin "7") (pinfunction "-VOUT_7") (pintype "output"))
      (node (ref "U5") (pin "1") (pinfunction "-VIN_1") (pintype "input"))
    )
    (net (code "59") (name "Net-(B1B-SYS_5V-PadP9.7)") (class "Default")
      (node (ref "B1") (pin "P9.7") (pinfunction "SYS_5V_P9.7") (pintype "bidirectional"))
      (node (ref "B1") (pin "P9.8") (pinfunction "SYS_5V_P9.8") (pintype "bidirectional"))
    )
    (net (code "60") (name "Net-(B1B-VDD_3V3-PadP9.3)") (class "Default")
      (node (ref "B1") (pin "P9.3") (pinfunction "VDD_3V3_P9.3") (pintype "bidirectional"))
      (node (ref "B1") (pin "P9.4") (pinfunction "VDD_3V3_P9.4") (pintype "bidirectional"))
    )
    (net (code "61") (name "Net-(CR1-CATHODE)") (class "Default")
      (node (ref "CR1") (pin "1") (pinfunction "CATHODE_1") (pintype "passive"))
      (node (ref "R18") (pin "1") (pinfunction "1_1") (pintype "passive"))
      (node (ref "R28") (pin "2") (pinfunction "2_2") (pintype "passive"))
    )
    (net (code "62") (name "Net-(CR2-CATHODE)") (class "Default")
      (node (ref "CR2") (pin "1") (pinfunction "CATHODE_1") (pintype "passive"))
      (node (ref "R17") (pin "1") (pinfunction "1_1") (pintype "passive"))
      (node (ref "R29") (pin "2") (pinfunction "2_2") (pintype "passive"))
    )
    (net (code "63") (name "Net-(CR3-CATHODE)") (class "Default")
      (node (ref "CR3") (pin "1") (pinfunction "CATHODE_1") (pintype "passive"))
      (node (ref "R21") (pin "1") (pinfunction "1_1") (pintype "passive"))
      (node (ref "R26") (pin "2") (pinfunction "2_2") (pintype "passive"))
    )
    (net (code "64") (name "Net-(CR4-CATHODE)") (class "Default")
      (node (ref "CR4") (pin "1") (pinfunction "CATHODE_1") (pintype "passive"))
      (node (ref "R22") (pin "1") (pinfunction "1_1") (pintype "passive"))
      (node (ref "R27") (pin "2") (pinfunction "2_2") (pintype "passive"))
    )
    (net (code "65") (name "Net-(CR6-CATHODE)") (class "Default")
      (node (ref "CR6") (pin "1") (pinfunction "CATHODE_1") (pintype "passive"))
      (node (ref "F4") (pin "2") (pinfunction "2_2") (pintype "passive"))
      (node (ref "K2") (pin "3") (pinfunction "3_3") (pintype "passive"))
      (node (ref "U15") (pin "1") (pinfunction "+VIN_1") (pintype "power_in"))
    )
    (net (code "66") (name "Net-(D1-K)") (class "Default")
      (node (ref "D1") (pin "C") (pinfunction "K_C") (pintype "passive"))
      (node (ref "K5") (pin "5") (pinfunction "5_5") (pintype "passive"))
      (node (ref "U7") (pin "7") (pinfunction "OUT_7") (pintype "output"))
    )
    (net (code "67") (name "Net-(D2-K)") (class "Default")
      (node (ref "D2") (pin "C") (pinfunction "K_C") (pintype "passive"))
      (node (ref "K4") (pin "5") (pinfunction "5_5") (pintype "passive"))
      (node (ref "U6") (pin "7") (pinfunction "OUT_7") (pintype "output"))
    )
    (net (code "68") (name "Net-(D3-K)") (class "Default")
      (node (ref "D3") (pin "C") (pinfunction "K_C") (pintype "passive"))
      (node (ref "K3") (pin "5") (pinfunction "5_5") (pintype "passive"))
      (node (ref "U4") (pin "7") (pinfunction "OUT_7") (pintype "output"))
    )
    (net (code "69") (name "Net-(D4-K)") (class "Default")
      (node (ref "D4") (pin "C") (pinfunction "K_C") (pintype "passive"))
      (node (ref "K1") (pin "5") (pinfunction "5_5") (pintype "passive"))
      (node (ref "U9") (pin "7") (pinfunction "OUT_7") (pintype "output"))
    )
    (net (code "70") (name "Net-(D5-K)") (class "Default")
      (node (ref "D5") (pin "C") (pinfunction "K_C") (pintype "passive"))
      (node (ref "K2") (pin "5") (pinfunction "5_5") (pintype "passive"))
      (node (ref "U16") (pin "7") (pinfunction "OUT_7") (pintype "output"))
    )
    (net (code "71") (name "Net-(D6-K)") (class "Default")
      (node (ref "D6") (pin "C") (pinfunction "K_C") (pintype "passive"))
      (node (ref "D7") (pin "C") (pinfunction "K_C") (pintype "passive"))
      (node (ref "D8") (pin "C") (pinfunction "K_C") (pintype "passive"))
      (node (ref "JP2") (pin "2") (pinfunction "2_2") (pintype "passive"))
      (node (ref "K6") (pin "5") (pinfunction "5_5") (pintype "passive"))
      (node (ref "K7") (pin "8") (pinfunction "8_8") (pintype "passive"))
      (node (ref "K8") (pin "COIL2") (pinfunction "COIL2_COIL2") (pintype "bidirectional"))
    )
    (net (code "72") (name "Net-(IC1-DVDT)") (class "Default")
      (node (ref "C19") (pin "1") (pinfunction "1_1") (pintype "passive"))
      (node (ref "IC1") (pin "6") (pinfunction "DVDT_6") (pintype "bidirectional"))
    )
    (net (code "73") (name "Net-(IC1-ILIM)") (class "Default")
      (node (ref "IC1") (pin "7") (pinfunction "ILIM_7") (pintype "bidirectional"))
      (node (ref "R46") (pin "2") (pinfunction "2_2") (pintype "passive"))
    )
    (net (code "74") (name "Net-(IC3-DVDT)") (class "Default")
      (node (ref "C22") (pin "1") (pinfunction "1_1") (pintype "passive"))
      (node (ref "IC3") (pin "6") (pinfunction "DVDT_6") (pintype "bidirectional"))
    )
    (net (code "75") (name "Net-(IC3-ILIM)") (class "Default")
      (node (ref "IC3") (pin "7") (pinfunction "ILIM_7") (pintype "bidirectional"))
      (node (ref "R47") (pin "2") (pinfunction "2_2") (pintype "passive"))
    )
    (net (code "76") (name "Net-(J3-Pad4)") (class "Default")
      (node (ref "J3") (pin "4") (pinfunction "4_4") (pintype "passive"))
      (node (ref "K3") (pin "2") (pinfunction "2_2") (pintype "passive"))
    )
    (net (code "77") (name "Net-(J3-Pad5)") (class "Default")
      (node (ref "J3") (pin "5") (pinfunction "5_5") (pintype "passive"))
      (node (ref "K4") (pin "2") (pinfunction "2_2") (pintype "passive"))
    )
    (net (code "78") (name "Net-(J3-Pad6)") (class "Default")
      (node (ref "J3") (pin "6") (pinfunction "6_6") (pintype "passive"))
      (node (ref "K5") (pin "2") (pinfunction "2_2") (pintype "passive"))
    )
    (net (code "79") (name "Net-(J4-Pad3)") (class "Default")
      (node (ref "J4") (pin "3") (pinfunction "3_3") (pintype "passive"))
      (node (ref "R13") (pin "2") (pinfunction "2_2") (pintype "passive"))
      (node (ref "R15") (pin "1") (pinfunction "1_1") (pintype "passive"))
      (node (ref "U3") (pin "1") (pinfunction "1_1") (pintype "passive"))
    )
    (net (code "80") (name "Net-(J4-Pad4)") (class "Default")
      (node (ref "J4") (pin "4") (pinfunction "4_4") (pintype "passive"))
      (node (ref "R14") (pin "2") (pinfunction "2_2") (pintype "passive"))
      (node (ref "R6") (pin "2") (pinfunction "2_2") (pintype "passive"))
      (node (ref "U3") (pin "2") (pinfunction "2_2") (pintype "passive"))
    )
    (net (code "81") (name "Net-(J6-Pad1)") (class "Default")
      (node (ref "J6") (pin "1") (pinfunction "1_1") (pintype "passive"))
      (node (ref "R41") (pin "1") (pinfunction "1_1") (pintype "passive"))
    )
    (net (code "82") (name "Net-(J6-Pad2)") (class "Default")
      (node (ref "J6") (pin "2") (pinfunction "2_2") (pintype "passive"))
      (node (ref "R39") (pin "1") (pinfunction "1_1") (pintype "passive"))
    )
    (net (code "83") (name "Net-(J6-Pad3)") (class "Default")
      (node (ref "J6") (pin "3") (pinfunction "3_3") (pintype "passive"))
      (node (ref "R35") (pin "1") (pinfunction "1_1") (pintype "passive"))
    )
    (net (code "84") (name "Net-(J6-Pad4)") (class "Default")
      (node (ref "J6") (pin "4") (pinfunction "4_4") (pintype "passive"))
      (node (ref "R34") (pin "1") (pinfunction "1_1") (pintype "passive"))
    )
    (net (code "85") (name "Net-(J8-Pad4)") (class "Default")
      (node (ref "J8") (pin "4") (pinfunction "4_4") (pintype "passive"))
      (node (ref "R17") (pin "2") (pinfunction "2_2") (pintype "passive"))
    )
    (net (code "86") (name "Net-(J8-Pad5)") (class "Default")
      (node (ref "J8") (pin "5") (pinfunction "5_5") (pintype "passive"))
      (node (ref "R18") (pin "2") (pinfunction "2_2") (pintype "passive"))
    )
    (net (code "87") (name "Net-(J8-Pad6)") (class "Default")
      (node (ref "J8") (pin "6") (pinfunction "6_6") (pintype "passive"))
      (node (ref "R21") (pin "2") (pinfunction "2_2") (pintype "passive"))
    )
    (net (code "88") (name "Net-(J8-Pad7)") (class "Default")
      (node (ref "J8") (pin "7") (pinfunction "7_7") (pintype "passive"))
      (node (ref "R22") (pin "2") (pinfunction "2_2") (pintype "passive"))
    )
    (net (code "89") (name "Net-(LED1-PadC)") (class "Default")
      (node (ref "LED1") (pin "C") (pinfunction "C_C") (pintype "passive"))
      (node (ref "R43") (pin "1") (pinfunction "1_1") (pintype "passive"))
    )
    (net (code "90") (name "Net-(LED2-PadC)") (class "Default")
      (node (ref "LED2") (pin "C") (pinfunction "C_C") (pintype "passive"))
      (node (ref "R24") (pin "1") (pinfunction "1_1") (pintype "passive"))
    )
    (net (code "91") (name "Net-(LED3-PadC)") (class "Default")
      (node (ref "LED3") (pin "C") (pinfunction "C_C") (pintype "passive"))
      (node (ref "R31") (pin "1") (pinfunction "1_1") (pintype "passive"))
    )
    (net (code "92") (name "Net-(LED4-PadC)") (class "Default")
      (node (ref "LED4") (pin "C") (pinfunction "C_C") (pintype "passive"))
      (node (ref "R32") (pin "1") (pinfunction "1_1") (pintype "passive"))
    )
    (net (code "93") (name "Net-(LED5-PadC)") (class "Default")
      (node (ref "LED5") (pin "C") (pinfunction "C_C") (pintype "passive"))
      (node (ref "R33") (pin "1") (pinfunction "1_1") (pintype "passive"))
    )
    (net (code "94") (name "Net-(R14-Pad1)") (class "Default")
      (node (ref "R14") (pin "1") (pinfunction "1_1") (pintype "passive"))
      (node (ref "R15") (pin "2") (pinfunction "2_2") (pintype "passive"))
    )
    (net (code "95") (name "Net-(TP1-TP)") (class "Default")
      (node (ref "TP1") (pin "P$1") (pinfunction "TP_P$1") (pintype "input"))
      (node (ref "U4") (pin "3") (pinfunction "~{FAULT}_3") (pintype "output"))
    )
    (net (code "96") (name "Net-(TP2-TP)") (class "Default")
      (node (ref "TP2") (pin "P$1") (pinfunction "TP_P$1") (pintype "input"))
      (node (ref "U6") (pin "3") (pinfunction "~{FAULT}_3") (pintype "output"))
    )
    (net (code "97") (name "Net-(TP3-TP)") (class "Default")
      (node (ref "TP3") (pin "P$1") (pinfunction "TP_P$1") (pintype "input"))
      (node (ref "U7") (pin "3") (pinfunction "~{FAULT}_3") (pintype "output"))
    )
    (net (code "98") (name "Net-(TP4-TP)") (class "Default")
      (node (ref "TP4") (pin "P$1") (pinfunction "TP_P$1") (pintype "input"))
      (node (ref "U9") (pin "3") (pinfunction "~{FAULT}_3") (pintype "output"))
    )
    (net (code "99") (name "Net-(TP5-TP)") (class "Default")
      (node (ref "TP5") (pin "P$1") (pinfunction "TP_P$1") (pintype "input"))
      (node (ref "U16") (pin "3") (pinfunction "~{FAULT}_3") (pintype "output"))
    )
    (net (code "100") (name "Net-(TP7-TP)") (class "Default")
      (node (ref "R29") (pin "1") (pinfunction "1_1") (pintype "passive"))
      (node (ref "TP7") (pin "P$1") (pinfunction "TP_P$1") (pintype "input"))
      (node (ref "U13") (pin "3") (pinfunction "INA_3") (pintype "input"))
    )
    (net (code "101") (name "Net-(TP8-TP)") (class "Default")
      (node (ref "R28") (pin "1") (pinfunction "1_1") (pintype "passive"))
      (node (ref "TP8") (pin "P$1") (pinfunction "TP_P$1") (pintype "input"))
      (node (ref "U13") (pin "4") (pinfunction "INB_4") (pintype "input"))
    )
    (net (code "102") (name "Net-(TP9-TP)") (class "Default")
      (node (ref "R26") (pin "1") (pinfunction "1_1") (pintype "passive"))
      (node (ref "TP9") (pin "P$1") (pinfunction "TP_P$1") (pintype "input"))
      (node (ref "U13") (pin "5") (pinfunction "INC_5") (pintype "input"))
    )
    (net (code "103") (name "Net-(TP10-TP)") (class "Default")
      (node (ref "R27") (pin "1") (pinfunction "1_1") (pintype "passive"))
      (node (ref "TP10") (pin "P$1") (pinfunction "TP_P$1") (pintype "input"))
      (node (ref "U13") (pin "6") (pinfunction "IND_6") (pintype "input"))
    )
    (net (code "104") (name "Net-(TP13-TP)") (class "Default")
      (node (ref "R16") (pin "1") (pinfunction "1_1") (pintype "passive"))
      (node (ref "R6") (pin "1") (pinfunction "1_1") (pintype "passive"))
      (node (ref "TP13") (pin "P$1") (pinfunction "TP_P$1") (pintype "input"))
      (node (ref "U8") (pin "7") (pinfunction "B_7") (pintype "bidirectional"))
    )
    (net (code "105") (name "Net-(TP14-TP)") (class "Default")
      (node (ref "R13") (pin "1") (pinfunction "1_1") (pintype "passive"))
      (node (ref "R37") (pin "2") (pinfunction "2_2") (pintype "passive"))
      (node (ref "TP14") (pin "P$1") (pinfunction "TP_P$1") (pintype "input"))
      (node (ref "U8") (pin "6") (pinfunction "A_6") (pintype "bidirectional"))
    )
    (net (code "106") (name "Net-(TP16-TP)") (class "Default")
      (node (ref "JP2") (pin "1") (pinfunction "1_1") (pintype "passive"))
      (node (ref "TP16") (pin "P$1") (pinfunction "TP_P$1") (pintype "input"))
      (node (ref "U$1") (pin "+VOUT") (pinfunction "+VOUT_+VOUT") (pintype "bidirectional"))
    )
    (net (code "107") (name "Net-(TP17-TP)") (class "Default")
      (node (ref "D6") (pin "A") (pinfunction "A_A") (pintype "passive"))
      (node (ref "D7") (pin "A") (pinfunction "A_A") (pintype "passive"))
      (node (ref "D8") (pin "A") (pinfunction "A_A") (pintype "passive"))
      (node (ref "K6") (pin "1") (pinfunction "1_1") (pintype "passive"))
      (node (ref "K7") (pin "1") (pinfunction "1_1") (pintype "passive"))
      (node (ref "K8") (pin "COIL1") (pinfunction "COIL1_COIL1") (pintype "bidirectional"))
      (node (ref "TP17") (pin "P$1") (pinfunction "TP_P$1") (pintype "input"))
      (node (ref "U$1") (pin "-VOUT") (pinfunction "-VOUT_-VOUT") (pintype "bidirectional"))
    )
    (net (code "108") (name "Net-(TP42-TP)") (class "Default")
      (node (ref "F1") (pin "1") (pinfunction "1_1") (pintype "passive"))
      (node (ref "J7") (pin "2") (pinfunction "2_2") (pintype "passive"))
      (node (ref "TP42") (pin "P$1") (pinfunction "TP_P$1") (pintype "input"))
    )
    (net (code "109") (name "Net-(U4-CL)") (class "Default")
      (node (ref "R25") (pin "1") (pinfunction "1_1") (pintype "passive"))
      (node (ref "U4") (pin "4") (pinfunction "CL_4") (pintype "output"))
    )
    (net (code "110") (name "Net-(U4-DELAY)") (class "Default")
      (node (ref "R30") (pin "2") (pinfunction "2_2") (pintype "passive"))
      (node (ref "U4") (pin "5") (pinfunction "DELAY_5") (pintype "bidirectional"))
    )
    (net (code "111") (name "Net-(U6-CL)") (class "Default")
      (node (ref "R1") (pin "1") (pinfunction "1_1") (pintype "passive"))
      (node (ref "U6") (pin "4") (pinfunction "CL_4") (pintype "output"))
    )
    (net (code "112") (name "Net-(U6-DELAY)") (class "Default")
      (node (ref "R3") (pin "2") (pinfunction "2_2") (pintype "passive"))
      (node (ref "U6") (pin "5") (pinfunction "DELAY_5") (pintype "bidirectional"))
    )
    (net (code "113") (name "Net-(U7-CL)") (class "Default")
      (node (ref "R7") (pin "1") (pinfunction "1_1") (pintype "passive"))
      (node (ref "U7") (pin "4") (pinfunction "CL_4") (pintype "output"))
    )
    (net (code "114") (name "Net-(U7-DELAY)") (class "Default")
      (node (ref "R8") (pin "2") (pinfunction "2_2") (pintype "passive"))
      (node (ref "U7") (pin "5") (pinfunction "DELAY_5") (pintype "bidirectional"))
    )
    (net (code "115") (name "Net-(U9-CL)") (class "Default")
      (node (ref "R2") (pin "1") (pinfunction "1_1") (pintype "passive"))
      (node (ref "U9") (pin "4") (pinfunction "CL_4") (pintype "output"))
    )
    (net (code "116") (name "Net-(U9-DELAY)") (class "Default")
      (node (ref "R4") (pin "2") (pinfunction "2_2") (pintype "passive"))
      (node (ref "U9") (pin "5") (pinfunction "DELAY_5") (pintype "bidirectional"))
    )
    (net (code "117") (name "Net-(U16-CL)") (class "Default")
      (node (ref "R10") (pin "1") (pinfunction "1_1") (pintype "passive"))
      (node (ref "U16") (pin "4") (pinfunction "CL_4") (pintype "output"))
    )
    (net (code "118") (name "Net-(U16-DELAY)") (class "Default")
      (node (ref "R12") (pin "2") (pinfunction "2_2") (pintype "passive"))
      (node (ref "U16") (pin "5") (pinfunction "DELAY_5") (pintype "bidirectional"))
    )
    (net (code "119") (name "Net-(U23-LED0)") (class "Default")
      (node (ref "R41") (pin "2") (pinfunction "2_2") (pintype "passive"))
      (node (ref "U23") (pin "1") (pinfunction "LED0_1") (pintype "bidirectional"))
    )
    (net (code "120") (name "Net-(U23-LED1)") (class "Default")
      (node (ref "R39") (pin "2") (pinfunction "2_2") (pintype "passive"))
      (node (ref "U23") (pin "2") (pinfunction "LED1_2") (pintype "bidirectional"))
    )
    (net (code "121") (name "Net-(U23-LED2)") (class "Default")
      (node (ref "R35") (pin "2") (pinfunction "2_2") (pintype "passive"))
      (node (ref "U23") (pin "3") (pinfunction "LED2_3") (pintype "bidirectional"))
    )
    (net (code "122") (name "Net-(U23-LED3)") (class "Default")
      (node (ref "R34") (pin "2") (pinfunction "2_2") (pintype "passive"))
      (node (ref "U23") (pin "4") (pinfunction "LED3_4") (pintype "bidirectional"))
    )
    (net (code "123") (name "VCC") (class "Default")
      (node (ref "C10") (pin "1") (pinfunction "1_1") (pintype "passive"))
      (node (ref "C2") (pin "1") (pinfunction "1_1") (pintype "passive"))
      (node (ref "C3") (pin "1") (pinfunction "1_1") (pintype "passive"))
      (node (ref "C6") (pin "1") (pinfunction "1_1") (pintype "passive"))
      (node (ref "C7") (pin "1") (pinfunction "1_1") (pintype "passive"))
      (node (ref "C8") (pin "1") (pinfunction "1_1") (pintype "passive"))
      (node (ref "C9") (pin "1") (pinfunction "1_1") (pintype "passive"))
      (node (ref "CR15") (pin "1") (pinfunction "CATHODE_1") (pintype "passive"))
      (node (ref "J6") (pin "5") (pinfunction "5_5") (pintype "passive"))
      (node (ref "LED1") (pin "A") (pinfunction "A_A") (pintype "passive"))
      (node (ref "R23") (pin "2") (pinfunction "2_2") (pintype "passive"))
      (node (ref "R36") (pin "2") (pinfunction "2_2") (pintype "passive"))
      (node (ref "R38") (pin "2") (pinfunction "2_2") (pintype "passive"))
      (node (ref "R40") (pin "1") (pinfunction "1_1") (pintype "passive"))
      (node (ref "R42") (pin "2") (pinfunction "2_2") (pintype "passive"))
      (node (ref "R44") (pin "1") (pinfunction "1_1") (pintype "passive"))
      (node (ref "R45") (pin "1") (pinfunction "1_1") (pintype "passive"))
      (node (ref "R5") (pin "1") (pinfunction "1_1") (pintype "passive"))
      (node (ref "TP25") (pin "P$1") (pinfunction "TP_P$1") (pintype "input"))
      (node (ref "U10") (pin "2") (pinfunction "ADDR_2") (pintype "input"))
      (node (ref "U10") (pin "5") (pinfunction "VDD_5") (pintype "power_in"))
      (node (ref "U10") (pin "6") (pinfunction "~{RESET}_6") (pintype "input"))
      (node (ref "U10") (pin "7") (pinfunction "ADDR1_7") (pintype "input"))
      (node (ref "U11") (pin "10") (pinfunction "EN2_10") (pintype "input"))
      (node (ref "U11") (pin "16") (pinfunction "VCC2_16") (pintype "power_in"))
      (node (ref "U12") (pin "10") (pinfunction "EN2_10") (pintype "input"))
      (node (ref "U12") (pin "16") (pinfunction "VCC2_16") (pintype "power_in"))
      (node (ref "U13") (pin "10") (pinfunction "EN2_10") (pintype "input"))
      (node (ref "U13") (pin "16") (pinfunction "VCC2_16") (pintype "power_in"))
      (node (ref "U14") (pin "16") (pinfunction "V+_16") (pintype "power_in"))
      (node (ref "U18") (pin "8") (pinfunction "VCC_8") (pintype "power_in"))
      (node (ref "U21") (pin "3") (pinfunction "+VOUT_3") (pintype "output"))
      (node (ref "U22") (pin "1") (pinfunction "VCCA_1") (pintype "power_in"))
      (node (ref "U23") (pin "8") (pinfunction "VDD_8") (pintype "power_in"))
      (node (ref "U24") (pin "1") (pinfunction "VCCA_1") (pintype "power_in"))
      (node (ref "U8") (pin "3") (pinfunction "VDDA_3") (pintype "power_in"))
    )
    (net (code "124") (name "VCC{slash}2") (class "Default")
      (node (ref "C4") (pin "1") (pinfunction "1_1") (pintype "passive"))
      (node (ref "C5") (pin "1") (pinfunction "1_1") (pintype "passive"))
      (node (ref "CR12") (pin "1") (pinfunction "CATHODE_1") (pintype "passive"))
      (node (ref "R11") (pin "1") (pinfunction "1_1") (pintype "passive"))
      (node (ref "R9") (pin "1") (pinfunction "1_1") (pintype "passive"))
      (node (ref "TP6") (pin "P$1") (pinfunction "TP_P$1") (pintype "input"))
      (node (ref "U1") (pin "3") (pinfunction "+VOUT_3") (pintype "output"))
      (node (ref "U12") (pin "1") (pinfunction "VCC1_1") (pintype "power_in"))
      (node (ref "U12") (pin "7") (pinfunction "EN1_7") (pintype "input"))
      (node (ref "U13") (pin "1") (pinfunction "VCC1_1") (pintype "power_in"))
    )
    (net (code "125") (name "VSS") (class "Default")
      (node (ref "D12") (pin "1") (pinfunction "1_1") (pintype "passive"))
      (node (ref "F1") (pin "2") (pinfunction "2_2") (pintype "passive"))
      (node (ref "J5") (pin "1") (pinfunction "1_1") (pintype "passive"))
    )
    (net (code "126") (name "unconnected-(B1A-GPIO_8-PadP8.35)") (class "Default")
      (node (ref "B1") (pin "P8.35") (pinfunction "GPIO_8_P8.35") (pintype "bidirectional"))
    )
    (net (code "127") (name "unconnected-(B1A-GPIO_9-PadP8.33)") (class "Default")
      (node (ref "B1") (pin "P8.33") (pinfunction "GPIO_9_P8.33") (pintype "bidirectional"))
    )
    (net (code "128") (name "unconnected-(B1A-GPIO_10-PadP8.31)") (class "Default")
      (node (ref "B1") (pin "P8.31") (pinfunction "GPIO_10_P8.31") (pintype "bidirectional"))
    )
    (net (code "129") (name "unconnected-(B1A-GPIO_11-PadP8.32)") (class "Default")
      (node (ref "B1") (pin "P8.32") (pinfunction "GPIO_11_P8.32") (pintype "bidirectional"))
    )
    (net (code "130") (name "unconnected-(B1A-GPIO_22-PadP8.19)") (class "Default")
      (node (ref "B1") (pin "P8.19") (pinfunction "GPIO_22_P8.19") (pintype "bidirectional"))
    )
    (net (code "131") (name "unconnected-(B1A-GPIO_23-PadP8.13)") (class "Default")
      (node (ref "B1") (pin "P8.13") (pinfunction "GPIO_23_P8.13") (pintype "bidirectional"))
    )
    (net (code "132") (name "unconnected-(B1A-GPIO_27-PadP8.17)") (class "Default")
      (node (ref "B1") (pin "P8.17") (pinfunction "GPIO_27_P8.17") (pintype "bidirectional"))
    )
    (net (code "133") (name "unconnected-(B1A-GPIO_32-PadP8.25)") (class "Default")
      (node (ref "B1") (pin "P8.25") (pinfunction "GPIO_32_P8.25") (pintype "bidirectional"))
    )
    (net (code "134") (name "unconnected-(B1A-GPIO_33-PadP8.24)") (class "Default")
      (node (ref "B1") (pin "P8.24") (pinfunction "GPIO_33_P8.24") (pintype "bidirectional"))
    )
    (net (code "135") (name "unconnected-(B1A-GPIO_34-PadP8.5)") (class "Default")
      (node (ref "B1") (pin "P8.5") (pinfunction "GPIO_34_P8.5") (pintype "bidirectional"))
    )
    (net (code "136") (name "unconnected-(B1A-GPIO_35-PadP8.6)") (class "Default")
      (node (ref "B1") (pin "P8.6") (pinfunction "GPIO_35_P8.6") (pintype "bidirectional"))
    )
    (net (code "137") (name "unconnected-(B1A-GPIO_36-PadP8.23)") (class "Default")
      (node (ref "B1") (pin "P8.23") (pinfunction "GPIO_36_P8.23") (pintype "bidirectional"))
    )
    (net (code "138") (name "unconnected-(B1A-GPIO_37-PadP8.22)") (class "Default")
      (node (ref "B1") (pin "P8.22") (pinfunction "GPIO_37_P8.22") (pintype "bidirectional"))
    )
    (net (code "139") (name "unconnected-(B1A-GPIO_38-PadP8.3)") (class "Default")
      (node (ref "B1") (pin "P8.3") (pinfunction "GPIO_38_P8.3") (pintype "bidirectional"))
    )
    (net (code "140") (name "unconnected-(B1A-GPIO_39-PadP8.4)") (class "Default")
      (node (ref "B1") (pin "P8.4") (pinfunction "GPIO_39_P8.4") (pintype "bidirectional"))
    )
    (net (code "141") (name "unconnected-(B1A-GPIO_45-PadP8.11)") (class "Default")
      (node (ref "B1") (pin "P8.11") (pinfunction "GPIO_45_P8.11") (pintype "bidirectional"))
    )
    (net (code "142") (name "unconnected-(B1A-GPIO_62-PadP8.21)") (class "Default")
      (node (ref "B1") (pin "P8.21") (pinfunction "GPIO_62_P8.21") (pintype "bidirectional"))
    )
    (net (code "143") (name "unconnected-(B1A-GPIO_63-PadP8.20)") (class "Default")
      (node (ref "B1") (pin "P8.20") (pinfunction "GPIO_63_P8.20") (pintype "bidirectional"))
    )
    (net (code "144") (name "unconnected-(B1A-GPIO_66-PadP8.7)") (class "Default")
      (node (ref "B1") (pin "P8.7") (pinfunction "GPIO_66_P8.7") (pintype "bidirectional"))
    )
    (net (code "145") (name "unconnected-(B1A-GPIO_69-PadP8.9)") (class "Default")
      (node (ref "B1") (pin "P8.9") (pinfunction "GPIO_69_P8.9") (pintype "bidirectional"))
    )
    (net (code "146") (name "unconnected-(B1A-GPIO_78-PadP8.37)") (class "Default")
      (node (ref "B1") (pin "P8.37") (pinfunction "GPIO_78_P8.37") (pintype "bidirectional"))
    )
    (net (code "147") (name "unconnected-(B1A-GPIO_79-PadP8.38)") (class "Default")
      (node (ref "B1") (pin "P8.38") (pinfunction "GPIO_79_P8.38") (pintype "bidirectional"))
    )
    (net (code "148") (name "unconnected-(B1A-GPIO_80-PadP8.36)") (class "Default")
      (node (ref "B1") (pin "P8.36") (pinfunction "GPIO_80_P8.36") (pintype "bidirectional"))
    )
    (net (code "149") (name "unconnected-(B1A-GPIO_81-PadP8.34)") (class "Default")
      (node (ref "B1") (pin "P8.34") (pinfunction "GPIO_81_P8.34") (pintype "bidirectional"))
    )
    (net (code "150") (name "unconnected-(B1A-GPIO_86-PadP8.27)") (class "Default")
      (node (ref "B1") (pin "P8.27") (pinfunction "GPIO_86_P8.27") (pintype "bidirectional"))
    )
    (net (code "151") (name "unconnected-(B1A-GPIO_87-PadP8.29)") (class "Default")
      (node (ref "B1") (pin "P8.29") (pinfunction "GPIO_87_P8.29") (pintype "bidirectional"))
    )
    (net (code "152") (name "unconnected-(B1A-GPIO_88-PadP8.28)") (class "Default")
      (node (ref "B1") (pin "P8.28") (pinfunction "GPIO_88_P8.28") (pintype "bidirectional"))
    )
    (net (code "153") (name "unconnected-(B1A-GPIO_89-PadP8.30)") (class "Default")
      (node (ref "B1") (pin "P8.30") (pinfunction "GPIO_89_P8.30") (pintype "bidirectional"))
    )
    (net (code "154") (name "unconnected-(B1B-AIN0-PadP9.39)") (class "Default")
      (node (ref "B1") (pin "P9.39") (pinfunction "AIN0_P9.39") (pintype "bidirectional"))
    )
    (net (code "155") (name "unconnected-(B1B-AIN1-PadP9.40)") (class "Default")
      (node (ref "B1") (pin "P9.40") (pinfunction "AIN1_P9.40") (pintype "bidirectional"))
    )
    (net (code "156") (name "unconnected-(B1B-AIN2-PadP9.37)") (class "Default")
      (node (ref "B1") (pin "P9.37") (pinfunction "AIN2_P9.37") (pintype "bidirectional"))
    )
    (net (code "157") (name "unconnected-(B1B-AIN3-PadP9.38)") (class "Default")
      (node (ref "B1") (pin "P9.38") (pinfunction "AIN3_P9.38") (pintype "bidirectional"))
    )
    (net (code "158") (name "unconnected-(B1B-AIN4-PadP9.33)") (class "Default")
      (node (ref "B1") (pin "P9.33") (pinfunction "AIN4_P9.33") (pintype "bidirectional"))
    )
    (net (code "159") (name "unconnected-(B1B-AIN5-PadP9.36)") (class "Default")
      (node (ref "B1") (pin "P9.36") (pinfunction "AIN5_P9.36") (pintype "bidirectional"))
    )
    (net (code "160") (name "unconnected-(B1B-AIN6-PadP9.35)") (class "Default")
      (node (ref "B1") (pin "P9.35") (pinfunction "AIN6_P9.35") (pintype "bidirectional"))
    )
    (net (code "161") (name "unconnected-(B1B-GNDA_ADC-PadP9.34)") (class "Default")
      (node (ref "B1") (pin "P9.34") (pinfunction "GNDA_ADC_P9.34") (pintype "bidirectional"))
    )
    (net (code "162") (name "unconnected-(B1B-GPIO_2-PadP9.22)") (class "Default")
      (node (ref "B1") (pin "P9.22") (pinfunction "GPIO_2_P9.22") (pintype "bidirectional"))
    )
    (net (code "163") (name "unconnected-(B1B-GPIO_3-PadP9.21)") (class "Default")
      (node (ref "B1") (pin "P9.21") (pinfunction "GPIO_3_P9.21") (pintype "bidirectional"))
    )
    (net (code "164") (name "unconnected-(B1B-GPIO_4-PadP9.17)") (class "Default")
      (node (ref "B1") (pin "P9.17") (pinfunction "GPIO_4_P9.17") (pintype "bidirectional"))
    )
    (net (code "165") (name "unconnected-(B1B-GPIO_5-PadP9.18)") (class "Default")
      (node (ref "B1") (pin "P9.18") (pinfunction "GPIO_5_P9.18") (pintype "bidirectional"))
    )
    (net (code "166") (name "unconnected-(B1B-GPIO_7-PadP9.42)") (class "Default")
      (node (ref "B1") (pin "P9.42") (pinfunction "GPIO_7_P9.42") (pintype "bidirectional"))
    )
    (net (code "167") (name "unconnected-(B1B-GPIO_20-PadP9.41)") (class "Default")
      (node (ref "B1") (pin "P9.41") (pinfunction "GPIO_20_P9.41") (pintype "bidirectional"))
    )
    (net (code "168") (name "unconnected-(B1B-GPIO_30-PadP9.11)") (class "Default")
      (node (ref "B1") (pin "P9.11") (pinfunction "GPIO_30_P9.11") (pintype "bidirectional"))
    )
    (net (code "169") (name "unconnected-(B1B-GPIO_31-PadP9.13)") (class "Default")
      (node (ref "B1") (pin "P9.13") (pinfunction "GPIO_31_P9.13") (pintype "bidirectional"))
    )
    (net (code "170") (name "unconnected-(B1B-GPIO_40-PadP9.14)") (class "Default")
      (node (ref "B1") (pin "P9.14") (pinfunction "GPIO_40_P9.14") (pintype "bidirectional"))
    )
    (net (code "171") (name "unconnected-(B1B-GPIO_48-PadP9.15)") (class "Default")
      (node (ref "B1") (pin "P9.15") (pinfunction "GPIO_48_P9.15") (pintype "bidirectional"))
    )
    (net (code "172") (name "unconnected-(B1B-GPIO_51-PadP9.16)") (class "Default")
      (node (ref "B1") (pin "P9.16") (pinfunction "GPIO_51_P9.16") (pintype "bidirectional"))
    )
    (net (code "173") (name "unconnected-(B1B-GPIO_117-PadP9.25)") (class "Default")
      (node (ref "B1") (pin "P9.25") (pinfunction "GPIO_117_P9.25") (pintype "bidirectional"))
    )
    (net (code "174") (name "unconnected-(B1B-GPIO_120-PadP9.31)") (class "Default")
      (node (ref "B1") (pin "P9.31") (pinfunction "GPIO_120_P9.31") (pintype "bidirectional"))
    )
    (net (code "175") (name "unconnected-(B1B-GPIO_121-PadP9.29)") (class "Default")
      (node (ref "B1") (pin "P9.29") (pinfunction "GPIO_121_P9.29") (pintype "bidirectional"))
    )
    (net (code "176") (name "unconnected-(B1B-GPIO_122-PadP9.30)") (class "Default")
      (node (ref "B1") (pin "P9.30") (pinfunction "GPIO_122_P9.30") (pintype "bidirectional"))
    )
    (net (code "177") (name "unconnected-(B1B-GPIO_123-PadP9.28)") (class "Default")
      (node (ref "B1") (pin "P9.28") (pinfunction "GPIO_123_P9.28") (pintype "bidirectional"))
    )
    (net (code "178") (name "unconnected-(B1B-PWR_BUT-PadP9.9)") (class "Default")
      (node (ref "B1") (pin "P9.9") (pinfunction "PWR_BUT_P9.9") (pintype "bidirectional"))
    )
    (net (code "179") (name "unconnected-(B1B-SYS_RESET~{N}-PadP9.10)") (class "Default")
      (node (ref "B1") (pin "P9.10") (pinfunction "SYS_RESET~{N}_P9.10") (pintype "bidirectional"))
    )
    (net (code "180") (name "unconnected-(B1B-VDD_ADC-PadP9.32)") (class "Default")
      (node (ref "B1") (pin "P9.32") (pinfunction "VDD_ADC_P9.32") (pintype "bidirectional"))
    )
    (net (code "181") (name "unconnected-(J3-Pad3)") (class "Default")
      (node (ref "J3") (pin "3") (pinfunction "3_3") (pintype "passive"))
    )
    (net (code "182") (name "unconnected-(J3-Pad7)") (class "Default")
      (node (ref "J3") (pin "7") (pinfunction "7_7") (pintype "passive"))
    )
    (net (code "183") (name "unconnected-(J3-Pad8)") (class "Default")
      (node (ref "J3") (pin "8") (pinfunction "8_8") (pintype "passive"))
    )
    (net (code "184") (name "unconnected-(J8-Pad8)") (class "Default")
      (node (ref "J8") (pin "8") (pinfunction "8_8") (pintype "passive"))
    )
    (net (code "185") (name "unconnected-(K1-Pad4)") (class "Default")
      (node (ref "K1") (pin "4") (pinfunction "4_4") (pintype "passive"))
    )
    (net (code "186") (name "unconnected-(K2-Pad4)") (class "Default")
      (node (ref "K2") (pin "4") (pinfunction "4_4") (pintype "passive"))
    )
    (net (code "187") (name "unconnected-(K3-Pad4)") (class "Default")
      (node (ref "K3") (pin "4") (pinfunction "4_4") (pintype "passive"))
    )
    (net (code "188") (name "unconnected-(K4-Pad4)") (class "Default")
      (node (ref "K4") (pin "4") (pinfunction "4_4") (pintype "passive"))
    )
    (net (code "189") (name "unconnected-(K5-Pad4)") (class "Default")
      (node (ref "K5") (pin "4") (pinfunction "4_4") (pintype "passive"))
    )
    (net (code "190") (name "unconnected-(K6-Pad4)") (class "Default")
      (node (ref "K6") (pin "4") (pinfunction "4_4") (pintype "passive"))
    )
    (net (code "191") (name "unconnected-(PS1-TRIM-Pad6)") (class "Default")
      (node (ref "PS1") (pin "6") (pinfunction "TRIM_6") (pintype "passive"))
    )
    (net (code "192") (name "unconnected-(PS3-CTRL-Pad3)") (class "Default")
      (node (ref "PS3") (pin "3") (pinfunction "CTRL_3") (pintype "passive"))
    )
    (net (code "193") (name "unconnected-(PS3-TRIM-Pad5)") (class "Default")
      (node (ref "PS3") (pin "5") (pinfunction "TRIM_5") (pintype "passive"))
    )
    (net (code "194") (name "unconnected-(U$1-PadNC1)") (class "Default")
      (node (ref "U$1") (pin "NC1") (pinfunction "NC1_NC1") (pintype "bidirectional"))
    )
    (net (code "195") (name "unconnected-(U$1-PadNC2)") (class "Default")
      (node (ref "U$1") (pin "NC2") (pinfunction "NC2_NC2") (pintype "bidirectional"))
    )
    (net (code "196") (name "unconnected-(U$1-PadRC)") (class "Default")
      (node (ref "U$1") (pin "RC") (pinfunction "RC_RC") (pintype "bidirectional"))
    )
    (net (code "197") (name "unconnected-(U10-ALERT-Pad3)") (class "Default")
      (node (ref "U10") (pin "3") (pinfunction "ALERT_3") (pintype "output"))
    )
    (net (code "198") (name "unconnected-(U10-EPAD-Pad9)") (class "Default")
      (node (ref "U10") (pin "9") (pinfunction "EPAD_9") (pintype "passive"))
    )
    (net (code "199") (name "unconnected-(U11-INC-Pad12)") (class "Default")
      (node (ref "U11") (pin "12") (pinfunction "INC_12") (pintype "input"))
    )
    (net (code "200") (name "unconnected-(U11-IND-Pad11)") (class "Default")
      (node (ref "U11") (pin "11") (pinfunction "IND_11") (pintype "input"))
    )
    (net (code "201") (name "unconnected-(U11-OUTC-Pad5)") (class "Default")
      (node (ref "U11") (pin "5") (pinfunction "OUTC_5") (pintype "tri_state"))
    )
    (net (code "202") (name "unconnected-(U11-OUTD-Pad6)") (class "Default")
      (node (ref "U11") (pin "6") (pinfunction "OUTD_6") (pintype "tri_state"))
    )
    (net (code "203") (name "unconnected-(U13-NC-Pad7)") (class "Default")
      (node (ref "U13") (pin "7") (pinfunction "NC_7") (pintype "passive"))
    )
    (net (code "204") (name "unconnected-(U14-NC-Pad13)") (class "Default")
      (node (ref "U14") (pin "13") (pinfunction "NC_13") (pintype "no_connect"))
    )
    (net (code "205") (name "unconnected-(U14-O4-Pad9)") (class "Default")
      (node (ref "U14") (pin "9") (pinfunction "O4_9") (pintype "output"))
    )
    (net (code "206") (name "unconnected-(U18-NC-Pad2)") (class "Default")
      (node (ref "U18") (pin "2") (pinfunction "NC_2") (pintype "no_connect"))
    )
    (net (code "207") (name "unconnected-(U18-NC_2-Pad1)") (class "Default")
      (node (ref "U18") (pin "1") (pinfunction "NC_2_1") (pintype "no_connect"))
    )
    (net (code "208") (name "unconnected-(U19-VADJ-Pad6)") (class "Default")
      (node (ref "U19") (pin "6") (pinfunction "VADJ_6") (pintype "output"))
    )
    (net (code "209") (name "unconnected-(U20-R.C-Pad1)") (class "Default")
      (node (ref "U20") (pin "1") (pinfunction "R.C_1") (pintype "passive"))
    )
    (net (code "210") (name "unconnected-(U20-TRIM-Pad8)") (class "Default")
      (node (ref "U20") (pin "8") (pinfunction "TRIM_8") (pintype "passive"))
    )
    (net (code "211") (name "unconnected-(U22-NC-Pad9)") (class "Default")
      (node (ref "U22") (pin "9") (pinfunction "NC_9") (pintype "no_connect"))
    )
    (net (code "212") (name "unconnected-(U22-NC_2-Pad6)") (class "Default")
      (node (ref "U22") (pin "6") (pinfunction "NC_2_6") (pintype "no_connect"))
    )
    (net (code "213") (name "unconnected-(U23-EPAD-Pad9)") (class "Default")
      (node (ref "U23") (pin "9") (pinfunction "EPAD_9") (pintype "passive"))
    )
  )
)
